# Eload_Power_Module_Support_-_Gen_2_Rev_4.net
KiCad netlist of a schematic drawn in Altium Designer
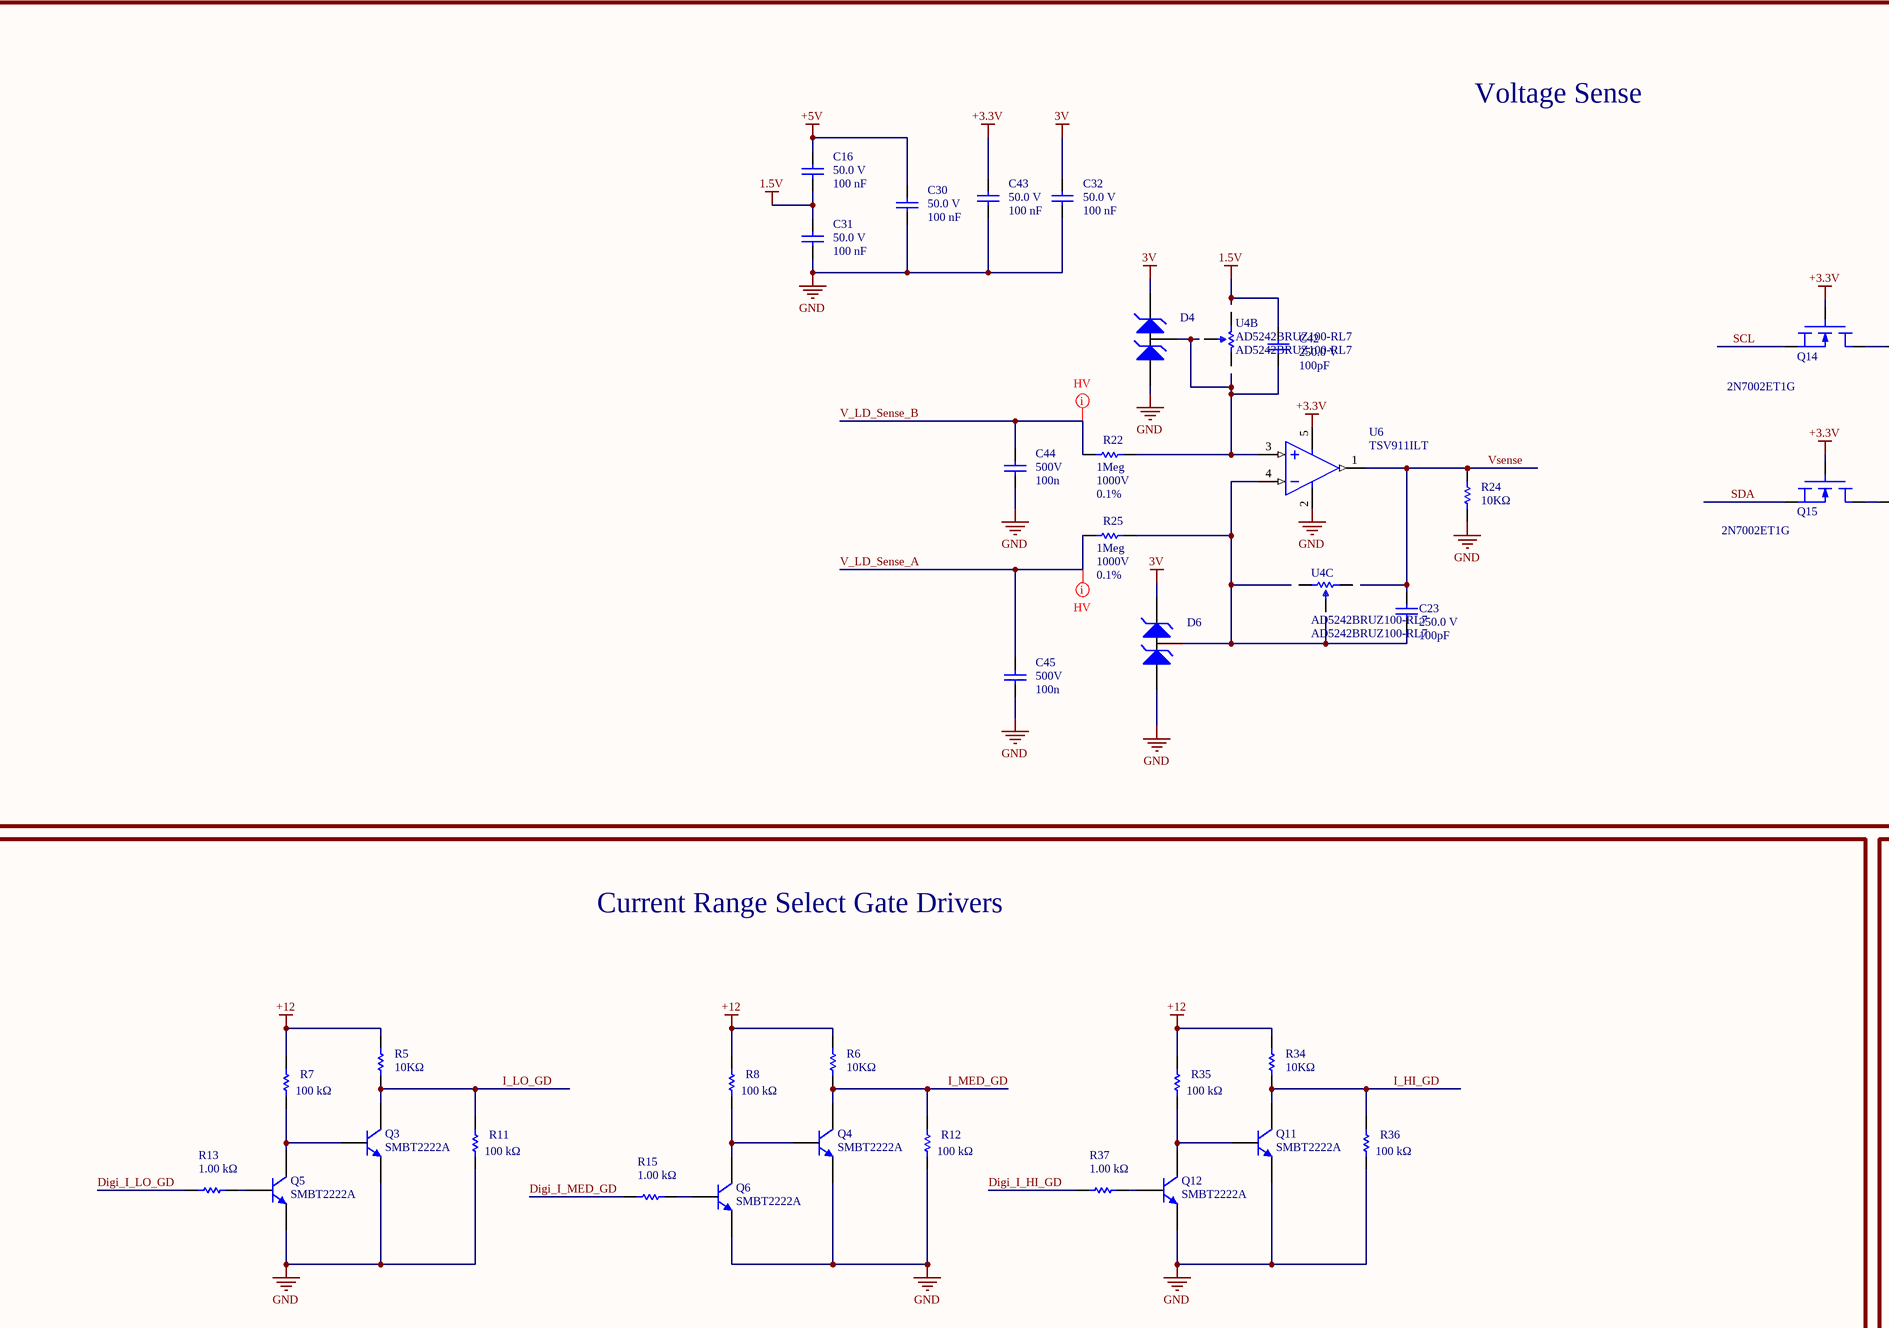
[diagram p0: Eload Power Module Support - Gen 2 Rev 4.SchDoc, top left]
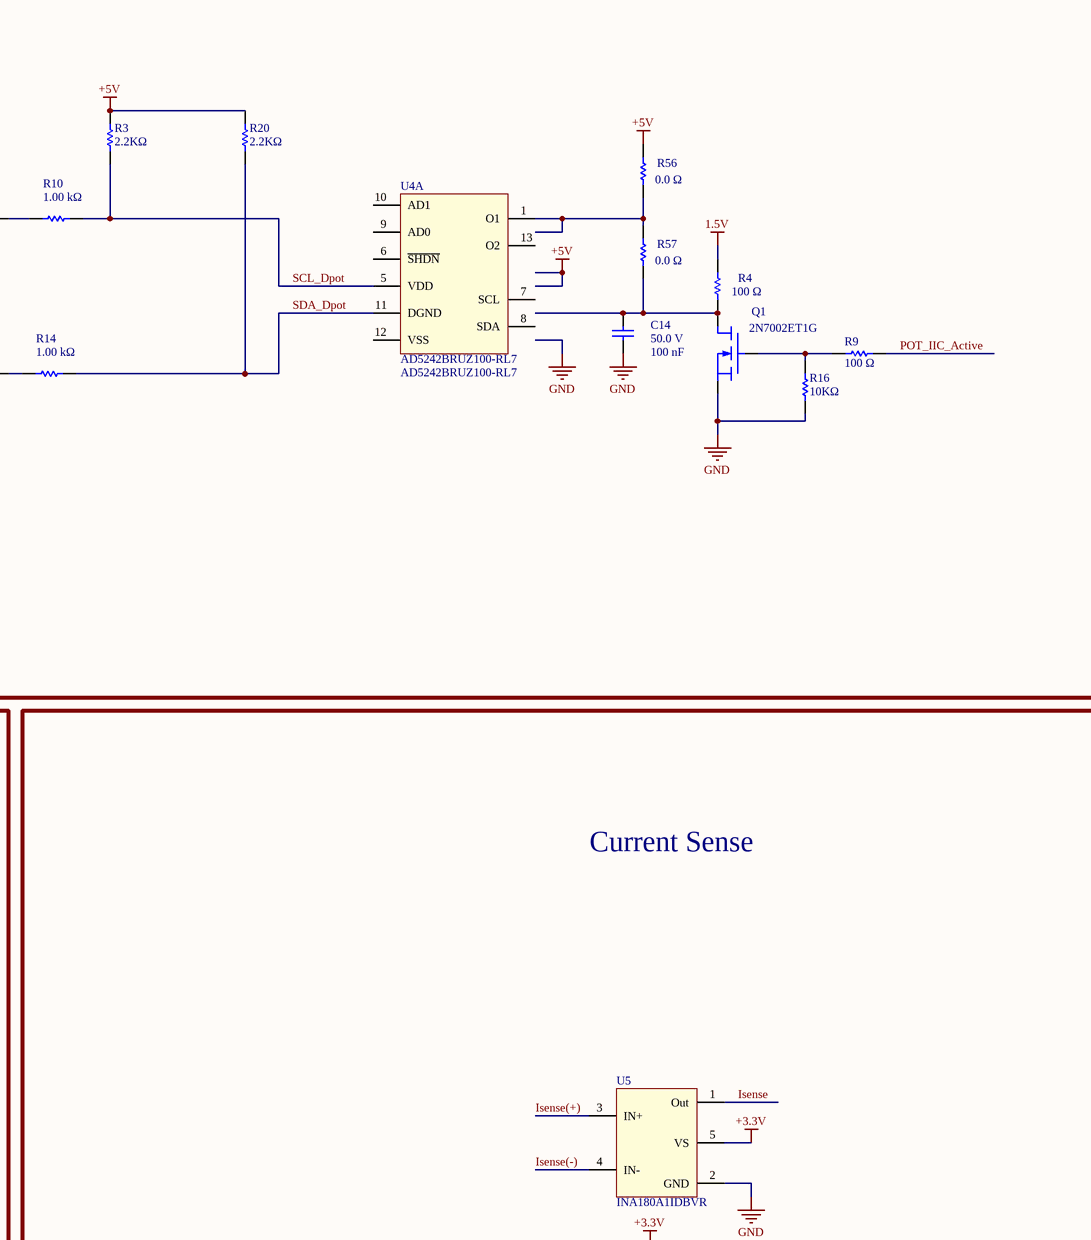
[diagram p1: Eload Power Module Support - Gen 2 Rev 4.SchDoc, top right]
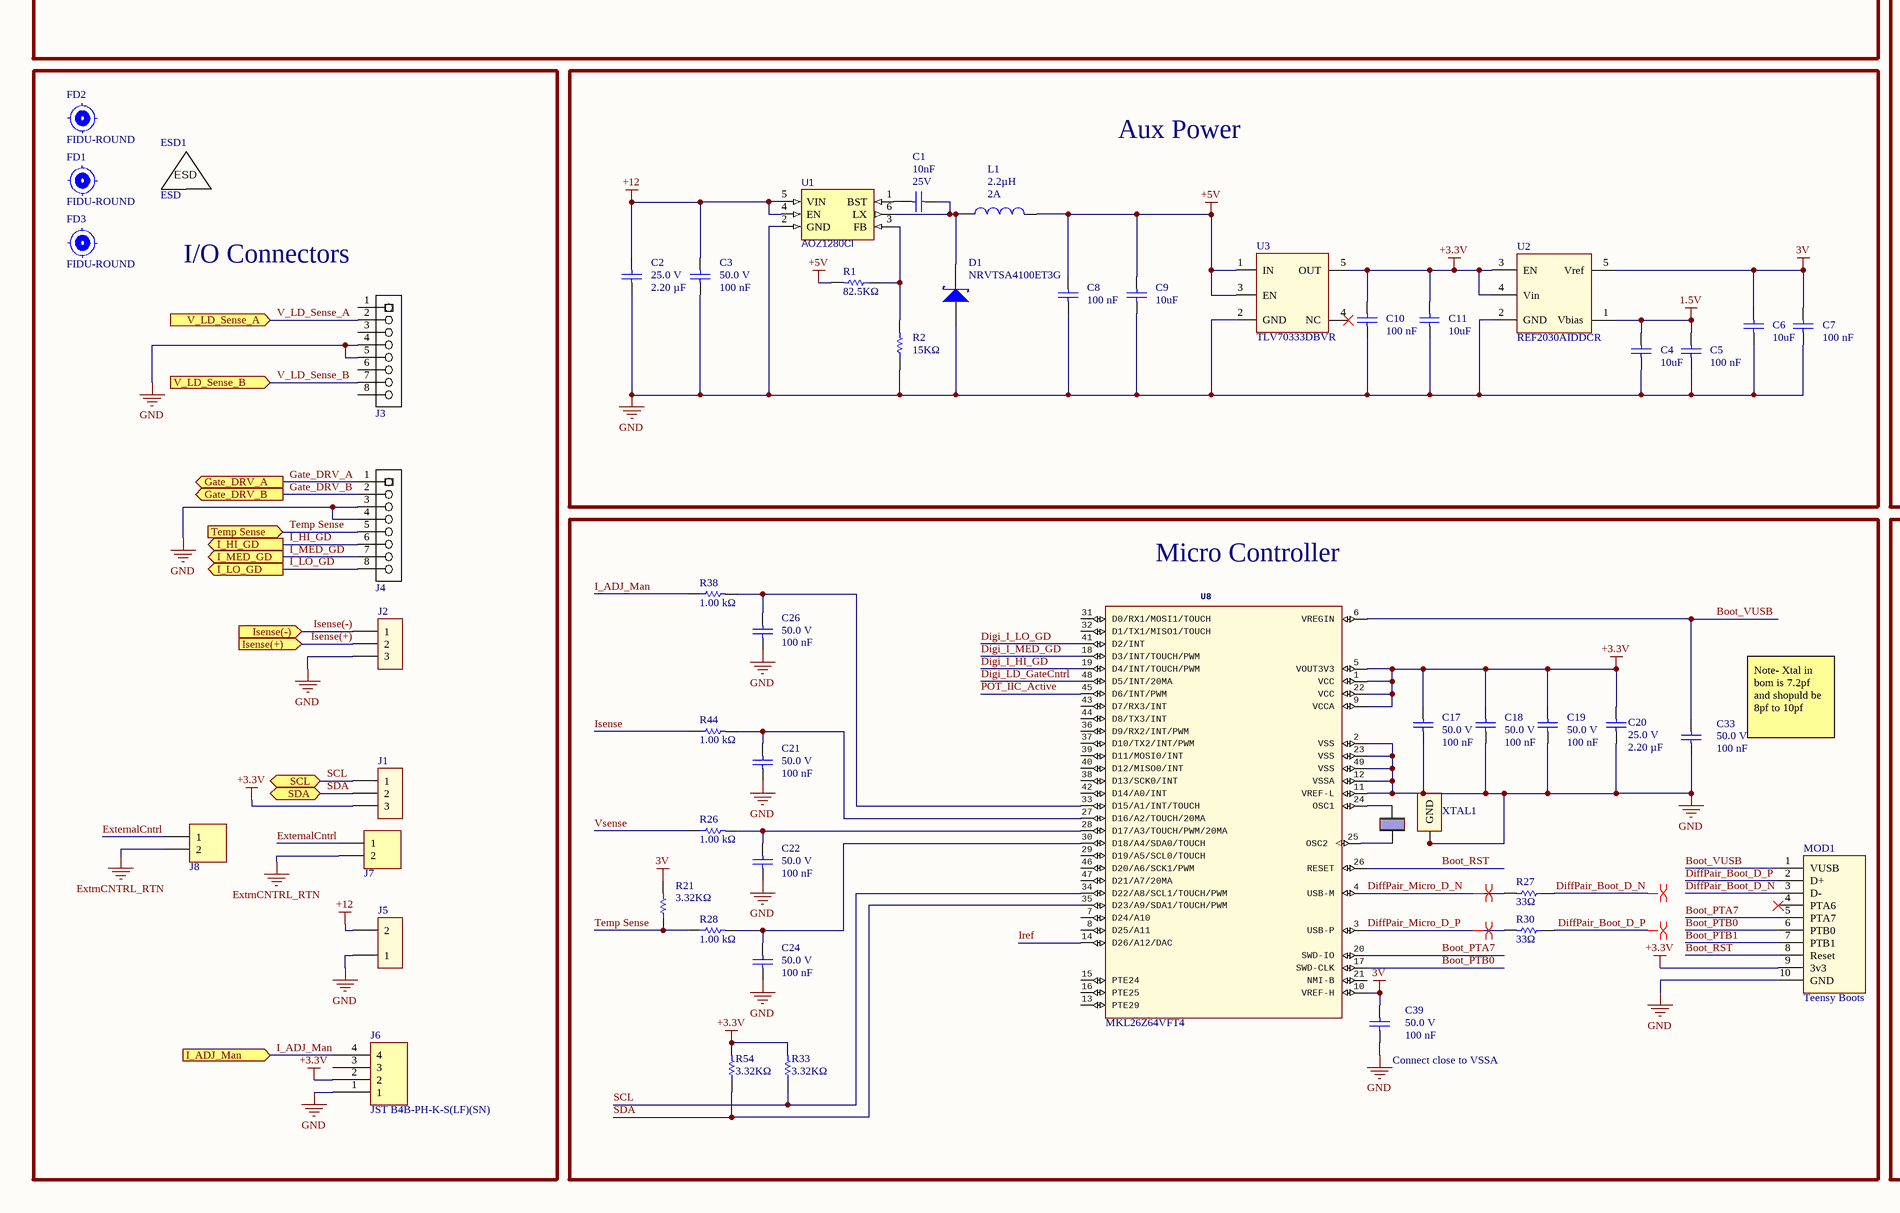
[diagram p2: Eload Power Module Support - Gen 2 Rev 4.SchDoc, bottom left]
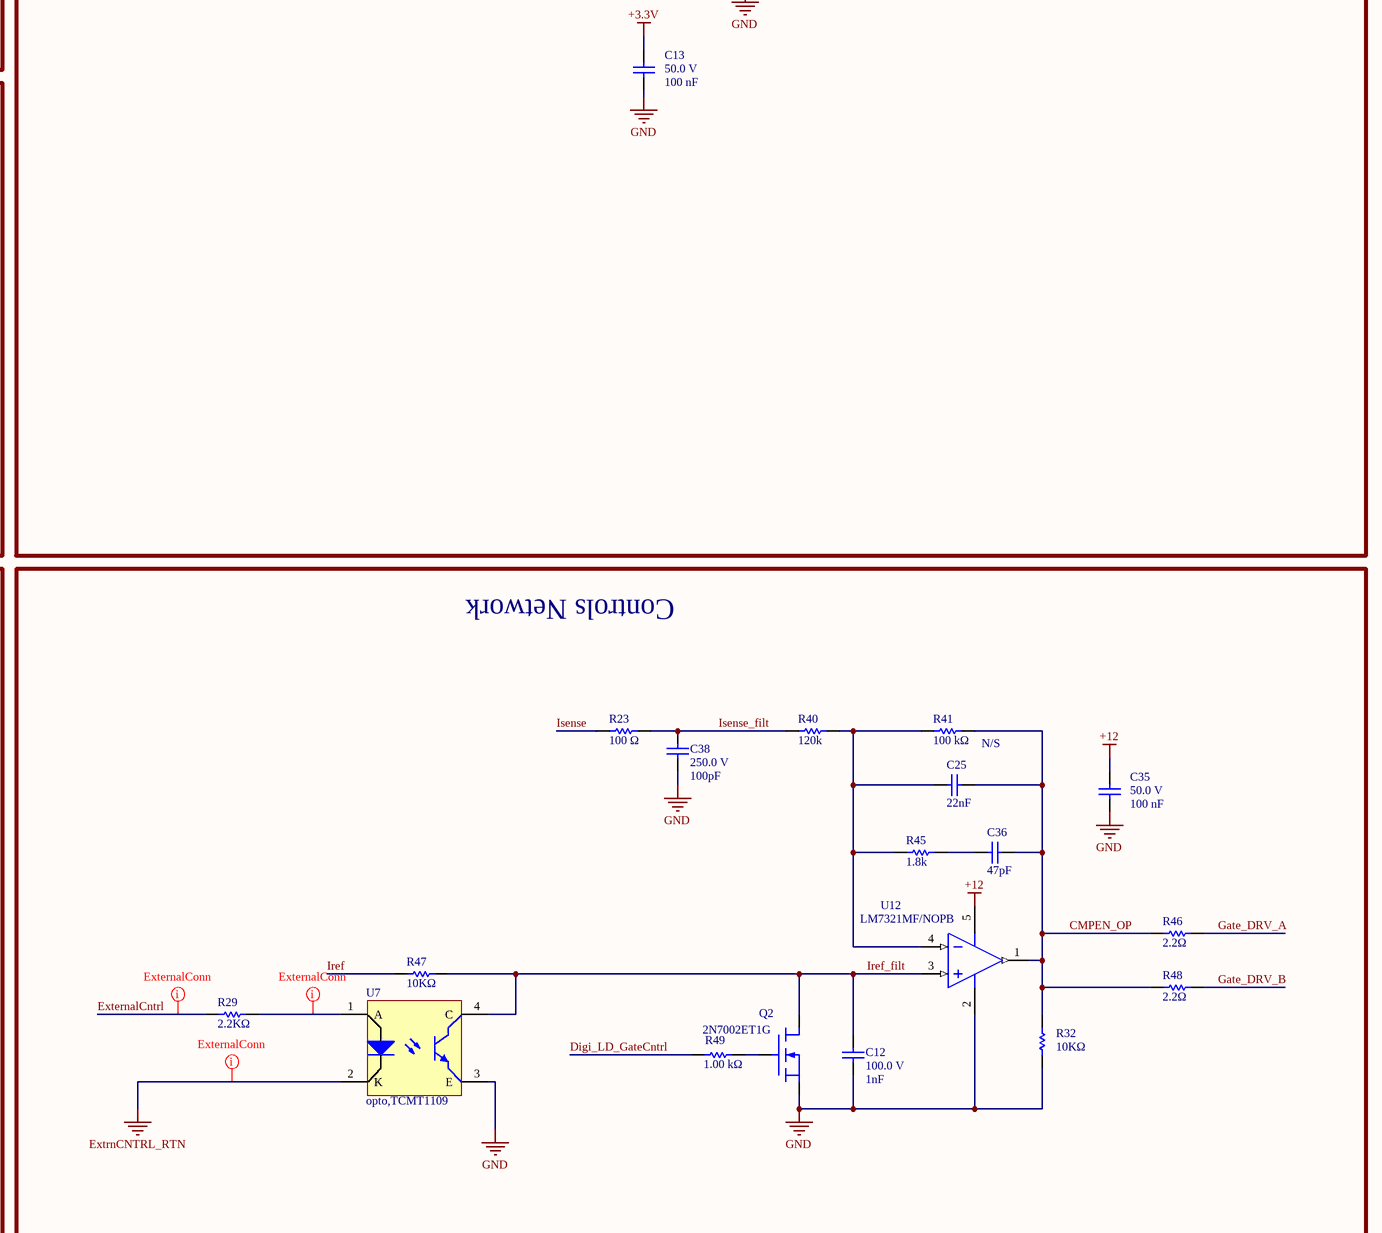
[diagram p3: Eload Power Module Support - Gen 2 Rev 4.SchDoc, bottom right]

(export (version "E")
  (design (tool "Eeschema 10.0.6"))
  (components
    (comp (ref "C1")
      (value "CL21B103KAANNNC")
      (footprint "Cap,0805")
      (description "CAP CER 10000PF 25V X7R 0805")
      (fields
        (field (name "MANUFACTURER") "Samsung Electro-Mechanics")
        (field (name "VOLTAGE RATING (DC)") "25V")
        (field (name "CAPACITANCE") "10nF")
      )
      (libsource (lib "Master Oct28_2018") (part "Cap,0805,10nF,±10%,25Vdc"))
    )
    (comp (ref "C2")
      (value "AVX 08053C225KAT2A")
      (footprint "CAP, 0805, HD")
      (description "0805 2.2 uF 25 V ±10 % Tolerance X7R SMT Multilayer Ceramic Capacitor")
      (fields
        (field (name "MANUFACTURER PART NUMBER") "08053C225KAT2A")
        (field (name "VOLTAGE RATING (DC)") "25.0 V")
        (field (name "CAPACITANCE") "2.20 µF")
      )
      (libsource (lib "Master Oct28_2018") (part "Cap,0805,2.2uF,25V,±10%"))
    )
    (comp (ref "C3")
      (value "08055C104JAT2A")
      (footprint "CAP, 0805, HD")
      (description "Capacitor; Ceramic; Cap 0.1 uF; Tol 5%; Vol-Rtg 50 VDC; SMT; 0805; X7R; Tape & Reel")
      (fields (field (name "VOLTAGE RATING (DC)") "50.0 V") (field (name "CAPACITANCE") "100 nF"))
      (libsource (lib "Master Oct28_2018") (part "Cap,0805,100nf,50V,5%,08055C104JAT2A"))
    )
    (comp (ref "C4")
      (value "Cap,0805,10uf,6.3V,10%,CL21A106KQFNNNG")
      (footprint "CAP, 0805, HD")
      (description "CL21 Series 10 uF 6.3V ±10 % Tolerance X5R SMT Multilayer Ceramic Capacitor")
      (fields (field (name "TOLERANCE") "±10%") (field (name "CAPACITANCE") "10uF"))
      (libsource (lib "Master Oct28_2018") (part "Cap,0805,10uf,6.3V,10%,CL21A106KQFNNNG"))
    )
    (comp (ref "C5")
      (value "08055C104JAT2A")
      (footprint "CAP, 0805, HD")
      (description "Capacitor; Ceramic; Cap 0.1 uF; Tol 5%; Vol-Rtg 50 VDC; SMT; 0805; X7R; Tape & Reel")
      (fields (field (name "CAPACITANCE") "100 nF"))
      (libsource (lib "Master Oct28_2018") (part "Cap,0805,100nf,50V,5%,08055C104JAT2A"))
    )
    (comp (ref "C6")
      (value "Cap,0805,10uf,6.3V,10%,CL21A106KQFNNNG")
      (footprint "CAP, 0805, HD")
      (description "CL21 Series 10 uF 6.3V ±10 % Tolerance X5R SMT Multilayer Ceramic Capacitor")
      (fields (field (name "TOLERANCE") "±10%") (field (name "CAPACITANCE") "10uF"))
      (libsource (lib "Master Oct28_2018") (part "Cap,0805,10uf,6.3V,10%,CL21A106KQFNNNG"))
    )
    (comp (ref "C7")
      (value "08055C104JAT2A")
      (footprint "CAP, 0805, HD")
      (description "Capacitor; Ceramic; Cap 0.1 uF; Tol 5%; Vol-Rtg 50 VDC; SMT; 0805; X7R; Tape & Reel")
      (fields (field (name "CAPACITANCE") "100 nF"))
      (libsource (lib "Master Oct28_2018") (part "Cap,0805,100nf,50V,5%,08055C104JAT2A"))
    )
    (comp (ref "C8")
      (value "08055C104JAT2A")
      (footprint "CAP, 0805, HD")
      (description "Capacitor; Ceramic; Cap 0.1 uF; Tol 5%; Vol-Rtg 50 VDC; SMT; 0805; X7R; Tape & Reel")
      (fields (field (name "CAPACITANCE") "100 nF"))
      (libsource (lib "Master Oct28_2018") (part "Cap,0805,100nf,50V,5%,08055C104JAT2A"))
    )
    (comp (ref "C9")
      (value "Cap,0805,10uf,6.3V,10%,CL21A106KQFNNNG")
      (footprint "CAP, 0805, HD")
      (description "CL21 Series 10 uF 6.3V ±10 % Tolerance X5R SMT Multilayer Ceramic Capacitor")
      (fields (field (name "TOLERANCE") "±10%") (field (name "CAPACITANCE") "10uF"))
      (libsource (lib "Master Oct28_2018") (part "Cap,0805,10uf,6.3V,10%,CL21A106KQFNNNG"))
    )
    (comp (ref "C10")
      (value "08055C104JAT2A")
      (footprint "CAP, 0805, HD")
      (description "Capacitor; Ceramic; Cap 0.1 uF; Tol 5%; Vol-Rtg 50 VDC; SMT; 0805; X7R; Tape & Reel")
      (fields (field (name "CAPACITANCE") "100 nF"))
      (libsource (lib "Master Oct28_2018") (part "Cap,0805,100nf,50V,5%,08055C104JAT2A"))
    )
    (comp (ref "C11")
      (value "Cap,0805,10uf,6.3V,10%,CL21A106KQFNNNG")
      (footprint "CAP, 0805, HD")
      (description "CL21 Series 10 uF 6.3V ±10 % Tolerance X5R SMT Multilayer Ceramic Capacitor")
      (fields (field (name "TOLERANCE") "±10%") (field (name "CAPACITANCE") "10uF"))
      (libsource (lib "Master Oct28_2018") (part "Cap,0805,10uf,6.3V,10%,CL21A106KQFNNNG"))
    )
    (comp (ref "C12")
      (value "Kemet C0805X102J1GACAUTO")
      (footprint "CAP, 0805, HD")
      (description "CAPACITOR, 1NF, 100V, NP0, 0805")
      (fields (field (name "VOLTAGE RATING (DC)") "100.0 V") (field (name "CAPACITANCE") "1nF"))
      (libsource (lib "Master SEPT2019") (part "Cap,0805,1nF,±5%,100Vdc"))
    )
    (comp (ref "C13")
      (value "08055C104JAT2A")
      (footprint "CAP, 0805, HD")
      (description "Capacitor; Ceramic; Cap 0.1 uF; Tol 5%; Vol-Rtg 50 VDC; SMT; 0805; X7R; Tape & Reel")
      (fields (field (name "VOLTAGE RATING (DC)") "50.0 V") (field (name "CAPACITANCE") "100 nF"))
      (libsource (lib "Master Oct28_2018") (part "Cap,0805,100nf,50V,5%,08055C104JAT2A"))
    )
    (comp (ref "C14")
      (value "08055C104JAT2A")
      (footprint "CAP, 0805, HD")
      (description "Capacitor; Ceramic; Cap 0.1 uF; Tol 5%; Vol-Rtg 50 VDC; SMT; 0805; X7R; Tape & Reel")
      (fields (field (name "VOLTAGE RATING (DC)") "50.0 V") (field (name "CAPACITANCE") "100 nF"))
      (libsource (lib "Master Oct28_2018") (part "Cap,0805,100nf,50V,5%,08055C104JAT2A"))
    )
    (comp (ref "C16")
      (value "08055C104JAT2A")
      (footprint "CAP, 0805, HD")
      (description "Capacitor; Ceramic; Cap 0.1 uF; Tol 5%; Vol-Rtg 50 VDC; SMT; 0805; X7R; Tape & Reel")
      (fields (field (name "VOLTAGE RATING (DC)") "50.0 V") (field (name "CAPACITANCE") "100 nF"))
      (libsource (lib "Master Oct28_2018") (part "Cap,0805,100nf,50V,5%,08055C104JAT2A"))
    )
    (comp (ref "C17")
      (value "Cap")
      (footprint "Cap,0805")
      (description "Capacitor; Ceramic; Cap 0.1 uF; Tol 5%; Vol-Rtg 50 VDC; SMT; 0805; X7R; Tape & Reel")
      (fields
        (field (name "MANUFACTURER PART NUMBER") "08055C104JAT2A")
        (field (name "VOLTAGE RATING (DC)") "50.0 V")
        (field (name "CAPACITANCE") "100 nF")
      )
      (libsource (lib "Master JULY2019") (part "Cap,0805,100nf,50V,5%,08055C104JAT2A"))
    )
    (comp (ref "C18")
      (value "Cap")
      (footprint "Cap,0805")
      (description "Capacitor; Ceramic; Cap 0.1 uF; Tol 5%; Vol-Rtg 50 VDC; SMT; 0805; X7R; Tape & Reel")
      (fields
        (field (name "MANUFACTURER PART NUMBER") "08055C104JAT2A")
        (field (name "VOLTAGE RATING (DC)") "50.0 V")
        (field (name "CAPACITANCE") "100 nF")
      )
      (libsource (lib "Master JULY2019") (part "Cap,0805,100nf,50V,5%,08055C104JAT2A"))
    )
    (comp (ref "C19")
      (value "Cap")
      (footprint "Cap,0805")
      (description "Capacitor; Ceramic; Cap 0.1 uF; Tol 5%; Vol-Rtg 50 VDC; SMT; 0805; X7R; Tape & Reel")
      (fields
        (field (name "MANUFACTURER PART NUMBER") "08055C104JAT2A")
        (field (name "VOLTAGE RATING (DC)") "50.0 V")
        (field (name "CAPACITANCE") "100 nF")
      )
      (libsource (lib "Master JULY2019") (part "Cap,0805,100nf,50V,5%,08055C104JAT2A"))
    )
    (comp (ref "C20")
      (value "AVX 08053C225KAT2A")
      (footprint "CAP, 0805, HD")
      (description "0805 2.2 uF 25 V ±10 % Tolerance X7R SMT Multilayer Ceramic Capacitor")
      (fields
        (field (name "MANUFACTURER PART NUMBER") "08053C225KAT2A")
        (field (name "VOLTAGE RATING (DC)") "25.0 V")
        (field (name "CAPACITANCE") "2.20 µF")
      )
      (libsource (lib "Master JULY2019") (part "Cap,0805,2.2uF,±10%,25V,08053C225KAT2A"))
    )
    (comp (ref "C21")
      (value "08055C104JAT2A")
      (footprint "CAP, 0805, HD")
      (description "Capacitor; Ceramic; Cap 0.1 uF; Tol 5%; Vol-Rtg 50 VDC; SMT; 0805; X7R; Tape & Reel")
      (fields (field (name "VOLTAGE RATING (DC)") "50.0 V") (field (name "CAPACITANCE") "100 nF"))
      (libsource (lib "Master Oct28_2018") (part "Cap,0805,100nf,50V,5%,08055C104JAT2A"))
    )
    (comp (ref "C22")
      (value "08055C104JAT2A")
      (footprint "CAP, 0805, HD")
      (description "Capacitor; Ceramic; Cap 0.1 uF; Tol 5%; Vol-Rtg 50 VDC; SMT; 0805; X7R; Tape & Reel")
      (fields (field (name "VOLTAGE RATING (DC)") "50.0 V") (field (name "CAPACITANCE") "100 nF"))
      (libsource (lib "Master Oct28_2018") (part "Cap,0805,100nf,50V,5%,08055C104JAT2A"))
    )
    (comp (ref "C23")
      (value "Cap")
      (footprint "Cap,0805")
      (description "CAP CER 100PF 250V 5% NP0 0805")
      (fields (field (name "VOLTAGE RATING (DC)") "250.0 V") (field (name "CAPACITANCE") "100pF"))
      (libsource (lib "Master JULY2019") (part "Cap,0805,100pf,250V,5%,GRM21A5C2E101JW01D"))
    )
    (comp (ref "C24")
      (value "08055C104JAT2A")
      (footprint "CAP, 0805, HD")
      (description "Capacitor; Ceramic; Cap 0.1 uF; Tol 5%; Vol-Rtg 50 VDC; SMT; 0805; X7R; Tape & Reel")
      (fields (field (name "VOLTAGE RATING (DC)") "50.0 V") (field (name "CAPACITANCE") "100 nF"))
      (libsource (lib "Master Oct28_2018") (part "Cap,0805,100nf,50V,5%,08055C104JAT2A"))
    )
    (comp (ref "C25")
      (value "Cap")
      (footprint "CAP, 0805, HD")
      (fields (field (name "CAP") "22nF"))
      (libsource (lib "Master SEPT2019") (part "CAP,0805,Generic"))
    )
    (comp (ref "C26")
      (value "08055C104JAT2A")
      (footprint "CAP, 0805, HD")
      (description "Capacitor; Ceramic; Cap 0.1 uF; Tol 5%; Vol-Rtg 50 VDC; SMT; 0805; X7R; Tape & Reel")
      (fields (field (name "VOLTAGE RATING (DC)") "50.0 V") (field (name "CAPACITANCE") "100 nF"))
      (libsource (lib "Master Oct28_2018") (part "Cap,0805,100nf,50V,5%,08055C104JAT2A"))
    )
    (comp (ref "C30")
      (value "08055C104JAT2A")
      (footprint "CAP, 0805, HD")
      (description "Capacitor; Ceramic; Cap 0.1 uF; Tol 5%; Vol-Rtg 50 VDC; SMT; 0805; X7R; Tape & Reel")
      (fields (field (name "VOLTAGE RATING (DC)") "50.0 V") (field (name "CAPACITANCE") "100 nF"))
      (libsource (lib "Master Oct28_2018") (part "Cap,0805,100nf,50V,5%,08055C104JAT2A"))
    )
    (comp (ref "C31")
      (value "08055C104JAT2A")
      (footprint "CAP, 0805, HD")
      (description "Capacitor; Ceramic; Cap 0.1 uF; Tol 5%; Vol-Rtg 50 VDC; SMT; 0805; X7R; Tape & Reel")
      (fields (field (name "VOLTAGE RATING (DC)") "50.0 V") (field (name "CAPACITANCE") "100 nF"))
      (libsource (lib "Master Oct28_2018") (part "Cap,0805,100nf,50V,5%,08055C104JAT2A"))
    )
    (comp (ref "C32")
      (value "08055C104JAT2A")
      (footprint "CAP, 0805, HD")
      (description "Capacitor; Ceramic; Cap 0.1 uF; Tol 5%; Vol-Rtg 50 VDC; SMT; 0805; X7R; Tape & Reel")
      (fields (field (name "VOLTAGE RATING (DC)") "50.0 V") (field (name "CAPACITANCE") "100 nF"))
      (libsource (lib "Master Oct28_2018") (part "Cap,0805,100nf,50V,5%,08055C104JAT2A"))
    )
    (comp (ref "C33")
      (value "Cap")
      (footprint "Cap,0805")
      (description "Capacitor; Ceramic; Cap 0.1 uF; Tol 5%; Vol-Rtg 50 VDC; SMT; 0805; X7R; Tape & Reel")
      (fields
        (field (name "MANUFACTURER PART NUMBER") "08055C104JAT2A")
        (field (name "VOLTAGE RATING (DC)") "50.0 V")
        (field (name "CAPACITANCE") "100 nF")
      )
      (libsource (lib "Master JULY2019") (part "Cap,0805,100nf,50V,5%,08055C104JAT2A"))
    )
    (comp (ref "C35")
      (value "08055C104JAT2A")
      (footprint "CAP, 0805, HD")
      (description "Capacitor; Ceramic; Cap 0.1 uF; Tol 5%; Vol-Rtg 50 VDC; SMT; 0805; X7R; Tape & Reel")
      (fields (field (name "VOLTAGE RATING (DC)") "50.0 V") (field (name "CAPACITANCE") "100 nF"))
      (libsource (lib "Master Oct28_2018") (part "Cap,0805,100nf,50V,5%,08055C104JAT2A"))
    )
    (comp (ref "C36")
      (value "Cap")
      (footprint "CAP, 0805, HD")
      (fields (field (name "CAP") "47pF"))
      (libsource (lib "Master SEPT2019") (part "CAP,0805,Generic"))
    )
    (comp (ref "C38")
      (value "Cap")
      (footprint "Cap,0805")
      (description "CAP CER 100PF 250V 5% NP0 0805")
      (fields (field (name "VOLTAGE RATING (DC)") "250.0 V") (field (name "CAPACITANCE") "100pF"))
      (libsource (lib "Master JULY2019") (part "Cap,0805,100pf,250V,5%,GRM21A5C2E101JW01D"))
    )
    (comp (ref "C39")
      (value "Cap")
      (footprint "Cap,0805")
      (description "Capacitor; Ceramic; Cap 0.1 uF; Tol 5%; Vol-Rtg 50 VDC; SMT; 0805; X7R; Tape & Reel")
      (fields
        (field (name "MANUFACTURER PART NUMBER") "08055C104JAT2A")
        (field (name "VOLTAGE RATING (DC)") "50.0 V")
        (field (name "CAPACITANCE") "100 nF")
      )
      (libsource (lib "Master JULY2019") (part "Cap,0805,100nf,50V,5%,08055C104JAT2A"))
    )
    (comp (ref "C42")
      (value "Cap")
      (footprint "Cap,0805")
      (description "CAP CER 100PF 250V 5% NP0 0805")
      (fields (field (name "VOLTAGE RATING (DC)") "250.0 V") (field (name "CAPACITANCE") "100pF"))
      (libsource (lib "Master JULY2019") (part "Cap,0805,100pf,250V,5%,GRM21A5C2E101JW01D"))
    )
    (comp (ref "C43")
      (value "08055C104JAT2A")
      (footprint "CAP, 0805, HD")
      (description "Capacitor; Ceramic; Cap 0.1 uF; Tol 5%; Vol-Rtg 50 VDC; SMT; 0805; X7R; Tape & Reel")
      (fields (field (name "VOLTAGE RATING (DC)") "50.0 V") (field (name "CAPACITANCE") "100 nF"))
      (libsource (lib "Master Oct28_2018") (part "Cap,0805,100nf,50V,5%,08055C104JAT2A"))
    )
    (comp (ref "C44")
      (value "Cap")
      (footprint "Cap,1210")
      (fields (field (name "CAP") "100n") (field (name "VOLT") "500V"))
      (libsource (lib "Master SEPT2019") (part "CAP,1210,Generic"))
    )
    (comp (ref "C45")
      (value "Cap")
      (footprint "Cap,1210")
      (fields (field (name "CAP") "100n") (field (name "VOLT") "500V"))
      (libsource (lib "Master SEPT2019") (part "CAP,1210,Generic"))
    )
    (comp (ref "D1")
      (value "NRVTSA4100ET3G")
      (footprint "DO-214AC, SMA")
      (description "Trench Schottky Rectifier, Very Low Leakage, 100V, 4A")
      (fields (field (name "MFG ~{P}N") "NRVTSA4100ET3G") (field (name "MANUFACTURER") "ON Semiconductor"))
      (libsource (lib "Master Oct28_2018") (part "Dio,Schottky,4A,400V,NRVTSA4100ET3G"))
    )
    (comp (ref "D4")
      (value "Diode")
      (footprint "SOT23-3")
      (fields (field (name "BASE PART NUMBER") "BAT54SL") (field (name "MANUFACTURER") "ON Semiconductor"))
      (libsource (lib "Master JULY2019") (part "Diode,Shottky,Array,Series,30V,200mA,BAT54SLT1G"))
    )
    (comp (ref "D6")
      (value "Diode")
      (footprint "SOT23-3")
      (fields (field (name "BASE PART NUMBER") "BAT54SL") (field (name "MANUFACTURER") "ON Semiconductor"))
      (libsource (lib "Master JULY2019") (part "Diode,Shottky,Array,Series,30V,200mA,BAT54SLT1G"))
    )
    (comp (ref "ESD1")
      (value "ESD")
      (footprint "ESDSILK")
      (description "ESD LOGO")
      (libsource (lib "TH Mechanical") (part "ESD"))
    )
    (comp (ref "FD1")
      (value "FIDU-ROUND")
      (footprint "FIDU-ROUND")
      (description "ROUND FIDUCIAL")
      (libsource (lib "TH Mechanical") (part "FIDU-ROUND"))
    )
    (comp (ref "FD2")
      (value "FIDU-ROUND")
      (footprint "FIDU-ROUND")
      (description "ROUND FIDUCIAL")
      (libsource (lib "TH Mechanical") (part "FIDU-ROUND"))
    )
    (comp (ref "FD3")
      (value "FIDU-ROUND")
      (footprint "FIDU-ROUND")
      (description "ROUND FIDUCIAL")
      (libsource (lib "TH Mechanical") (part "FIDU-ROUND"))
    )
    (comp (ref "J1")
      (value "Generic Header")
      (footprint "Header,3POS,0.1\",RA")
      (description "Generic Header 3 pos header 0.1\"")
      (libsource (lib "Master JULY2019") (part "Header 1x3,0.1{dblquote},TH,Generic"))
    )
    (comp (ref "J2")
      (value "Generic Header")
      (footprint "Header,3POS,0.1\",RA")
      (description "Generic Header 3 pos header 0.1\"")
      (libsource (lib "Master JULY2019") (part "Header 1x3,0.1{dblquote},TH,Generic"))
    )
    (comp (ref "J3")
      (value "HEADER,0.1\",8Pin,SinlgeRow")
      (footprint "Header,8Pin,SingleRow, RA,0.1\"")
      (libsource (lib "Master JULY2019") (part "HEADER,0.1{dblquote},8Pin,SinlgeRow"))
    )
    (comp (ref "J4")
      (value "HEADER,0.1\",8Pin,SinlgeRow")
      (footprint "Header,8Pin,SingleRow, RA,0.1\"")
      (libsource (lib "Master JULY2019") (part "HEADER,0.1{dblquote},8Pin,SinlgeRow"))
    )
    (comp (ref "J5")
      (value "Generic Header")
      (footprint "HEADER-1X2,0.1\",RA1")
      (libsource (lib "Master JULY2019") (part "Header 1x2,0.1{dblquote}Spacing"))
    )
    (comp (ref "J6")
      (value "JST B4B-PH-K-S(LF)(SN)")
      (footprint "Conn, JST, 4 pin, 2mm spacing")
      (description "PH Series 4 Position 2 mm Pitch Through Hole Crimp Top Entry Shrouded Header")
      (fields (field (name "MANUFACTURER PART NUMBER") "B4B-PH-K-S(LF)(SN)"))
      (libsource (lib "Master JULY2019") (part "Conntector, though hole, JST, 4pin, 2mm,B4B-PH-K-S(LF)(SN)"))
    )
    (comp (ref "J7")
      (value "conn, through hole, molex, 2 pin, 0.1\",640456-2")
      (footprint "Conn, Molex, 2pin,0.1\" spacing")
      (description "Header, Friction Lock; MTA-100; 2; 250 VAC; Polyester; Tin; Copper Alloy; Tin")
      (libsource (lib "Master JULY2019") (part "conn, through hole, molex, 2 pin, 0.1{dblquote},640456-2"))
    )
    (comp (ref "J8")
      (value "conn, through hole, molex, 2 pin, 0.1\",640456-2")
      (footprint "Conn, Molex, 2pin,0.1\" spacing")
      (description "Header, Friction Lock; MTA-100; 2; 250 VAC; Polyester; Tin; Copper Alloy; Tin")
      (libsource (lib "Master JULY2019") (part "conn, through hole, molex, 2 pin, 0.1{dblquote},640456-2"))
    )
    (comp (ref "L1")
      (value "CIGT252008LM2R2MNE")
      (footprint "IND,2520")
      (description "FIXED IND 2.2UH 2A 97MOHM SMD")
      (fields
        (field (name "MANUFACTURER") "Samsung Electro-Mechanics")
        (field (name "INDUCTANCE") "2.2µH")
        (field (name "TOLERANCE") "±20%")
        (field (name "CURRENT RATING (AMPS)") "2A")
      )
      (libsource (lib "Master Oct28_2018") (part "IND,2025,2.2u,2A,97mOhm,CIGT252008LM2R2MNE"))
    )
    (comp (ref "MOD1")
      (value "Teensy Boots")
      (footprint "Mod,Teensy Boots")
      (libsource (lib "Master SEPT2019") (part "Module,Teensy Boots,Programming"))
    )
    (comp (ref "Q1")
      (value "2N7002ET1G")
      (footprint "SOT23-3")
      (description "Small Signal MOSFET, 60 V, 310 mA, Single, N-Channel, 3-Pin SOT-23, Pb-Free, Tape and Reel")
      (fields
        (field (name "MANUFACTURER") "ON Semiconductor")
        (field (name "MANUFACTURER PART NUMBER") "2N7002ET1G")
      )
      (libsource (lib "Master JULY2019") (part "MOSFET,N-Channel,SOT23,0.25A,60V,2N7002ET1G"))
    )
    (comp (ref "Q2")
      (value "2N7002ET1G")
      (footprint "SOT23-3")
      (description "Small Signal MOSFET, 60 V, 310 mA, Single, N-Channel, 3-Pin SOT-23, Pb-Free, Tape and Reel")
      (fields
        (field (name "MANUFACTURER") "ON Semiconductor")
        (field (name "MANUFACTURER PART NUMBER") "2N7002ET1G")
      )
      (libsource (lib "Master JULY2019") (part "MOSFET,N-Channel,SOT23,0.25A,60V,2N7002ET1G"))
    )
    (comp (ref "Q3")
      (value "SMBT2222A")
      (footprint "SOT23-3")
      (description "NPN Silicon Switching Transistor, 40 V VCEO, 600 mA IC, SOT23, Reel, Green")
      (fields (field (name "MFG P/N") "SMBT2222A"))
      (libsource (lib "Master JULY2019") (part "Trans,40V,600mA,0.33W, SMBT2222A"))
    )
    (comp (ref "Q4")
      (value "SMBT2222A")
      (footprint "SOT23-3")
      (description "NPN Silicon Switching Transistor, 40 V VCEO, 600 mA IC, SOT23, Reel, Green")
      (fields (field (name "MFG P/N") "SMBT2222A"))
      (libsource (lib "Master JULY2019") (part "Trans,40V,600mA,0.33W, SMBT2222A"))
    )
    (comp (ref "Q5")
      (value "SMBT2222A")
      (footprint "SOT23-3")
      (description "NPN Silicon Switching Transistor, 40 V VCEO, 600 mA IC, SOT23, Reel, Green")
      (fields (field (name "MFG P/N") "SMBT2222A"))
      (libsource (lib "Master JULY2019") (part "Trans,40V,600mA,0.33W, SMBT2222A"))
    )
    (comp (ref "Q6")
      (value "SMBT2222A")
      (footprint "SOT23-3")
      (description "NPN Silicon Switching Transistor, 40 V VCEO, 600 mA IC, SOT23, Reel, Green")
      (fields (field (name "MFG P/N") "SMBT2222A"))
      (libsource (lib "Master JULY2019") (part "Trans,40V,600mA,0.33W, SMBT2222A"))
    )
    (comp (ref "Q11")
      (value "SMBT2222A")
      (footprint "SOT23-3")
      (description "NPN Silicon Switching Transistor, 40 V VCEO, 600 mA IC, SOT23, Reel, Green")
      (fields (field (name "MFG P/N") "SMBT2222A"))
      (libsource (lib "Master JULY2019") (part "Trans,40V,600mA,0.33W, SMBT2222A"))
    )
    (comp (ref "Q12")
      (value "SMBT2222A")
      (footprint "SOT23-3")
      (description "NPN Silicon Switching Transistor, 40 V VCEO, 600 mA IC, SOT23, Reel, Green")
      (fields (field (name "MFG P/N") "SMBT2222A"))
      (libsource (lib "Master JULY2019") (part "Trans,40V,600mA,0.33W, SMBT2222A"))
    )
    (comp (ref "Q14")
      (value "2N7002ET1G")
      (footprint "SOT23-3")
      (description "Small Signal MOSFET, 60 V, 310 mA, Single, N-Channel, 3-Pin SOT-23, Pb-Free, Tape and Reel")
      (fields
        (field (name "MANUFACTURER") "ON Semiconductor")
        (field (name "MANUFACTURER PART NUMBER") "2N7002ET1G")
      )
      (libsource (lib "Master JULY2019") (part "MOSFET,N-Channel,SOT23,0.25A,60V,2N7002ET1G"))
    )
    (comp (ref "Q15")
      (value "2N7002ET1G")
      (footprint "SOT23-3")
      (description "Small Signal MOSFET, 60 V, 310 mA, Single, N-Channel, 3-Pin SOT-23, Pb-Free, Tape and Reel")
      (fields
        (field (name "MANUFACTURER") "ON Semiconductor")
        (field (name "MANUFACTURER PART NUMBER") "2N7002ET1G")
      )
      (libsource (lib "Master JULY2019") (part "MOSFET,N-Channel,SOT23,0.25A,60V,2N7002ET1G"))
    )
    (comp (ref "R1")
      (value "TNPW080582K5BEEA")
      (footprint "res, 0805, HD")
      (fields
        (field (name "MANUFACTURER") "Vishay Dale")
        (field (name "TOLERANCE") "±0.1%")
        (field (name "RESISTANCE") "82.5KΩ")
      )
      (libsource (lib "Master JULY2019") (part "Res,0805,82.5KΩ,0.1%,25ppm, TNPW080582K5BEEA"))
    )
    (comp (ref "R2")
      (value "CRGCQ0805F15K")
      (footprint "res, 0805, HD")
      (fields (field (name "TOLERANCE") "±1%") (field (name "RESISTANCE") "15KΩ"))
      (libsource (lib "Master Oct28_2018") (part "Res,0805,15KΩ,1%,±100ppm/°C,CRGCQ0805F15K"))
    )
    (comp (ref "R3")
      (value "Res1")
      (footprint "res, 0805, HD")
      (description "RES SMD 2.2K OHM 1% 1/8W 0805")
      (fields (field (name "RESISTANCE") "2.2KΩ"))
      (libsource (lib "Master SEPT2019") (part "Res,0805,2.2KΩ,±1%,100.0 ppm/°C,150.0 V,CRCW08052K20FKEA"))
    )
    (comp (ref "R4")
      (value "CRCW0805100RJNEAC")
      (footprint "res, 0805, HD")
      (description "RES 100 OHM 5% 1/8W 0805")
      (fields (field (name "TOLERANCE") "±5%") (field (name "RESISTANCE") "100 Ω"))
      (libsource (lib "Master SEPT2019") (part "Res,0805,100Ω,5%,±200ppm/°C"))
    )
    (comp (ref "R5")
      (value "Vishay / Dale CRCW080510K0FKTA")
      (footprint "res, 0805, HD")
      (description "RES SMD 10K OHM 1% 1/8W 0805")
      (fields (field (name "RESISTANCE") "10KΩ"))
      (libsource (lib "Master Oct28_2018") (part "Res,0805,10.0kΩ,1%,100 ppm,CRCW080510K0FKTA"))
    )
    (comp (ref "R6")
      (value "Vishay / Dale CRCW080510K0FKTA")
      (footprint "res, 0805, HD")
      (description "RES SMD 10K OHM 1% 1/8W 0805")
      (fields (field (name "RESISTANCE") "10KΩ"))
      (libsource (lib "Master Oct28_2018") (part "Res,0805,10.0kΩ,1%,100 ppm,CRCW080510K0FKTA"))
    )
    (comp (ref "R7")
      (value "Res,0805,100kΩ,1%,100ppm,CRCW0805100KFKEA")
      (footprint "res, 0805, HD")
      (description "100 kOhms ±1% 0.125W, 1/8W Chip Resistor 0805 (2012 Metric) Thick Film")
      (fields
        (field (name "MANUFACTURER PART NUMBER") "CRCW0805100KFKEA")
        (field (name "MANUFACTURER") "Vishay")
        (field (name "RESISTANCE") "100 kΩ")
      )
      (libsource (lib "Master Oct28_2018") (part "Res,0805,100kΩ,1%,100ppm,CRCW0805100KFKEA"))
    )
    (comp (ref "R8")
      (value "Res,0805,100kΩ,1%,100ppm,CRCW0805100KFKEA")
      (footprint "res, 0805, HD")
      (description "100 kOhms ±1% 0.125W, 1/8W Chip Resistor 0805 (2012 Metric) Thick Film")
      (fields
        (field (name "MANUFACTURER PART NUMBER") "CRCW0805100KFKEA")
        (field (name "MANUFACTURER") "Vishay")
        (field (name "RESISTANCE") "100 kΩ")
      )
      (libsource (lib "Master Oct28_2018") (part "Res,0805,100kΩ,1%,100ppm,CRCW0805100KFKEA"))
    )
    (comp (ref "R9")
      (value "CRCW0805100RJNEAC")
      (footprint "res, 0805, HD")
      (description "RES 100 OHM 5% 1/8W 0805")
      (fields (field (name "TOLERANCE") "±5%") (field (name "RESISTANCE") "100 Ω"))
      (libsource (lib "Master SEPT2019") (part "Res,0805,100Ω,5%,±200ppm/°C"))
    )
    (comp (ref "R10")
      (value "Vishay CRCW08051K00JNEA")
      (footprint "res, 0805, HD")
      (description "Res Thick Film 0805 1K Ohm 5% 0.125W(1/8W) ±200ppm/C Molded SMD Automotive Paper T/R")
      (fields
        (field (name "MANUFACTURER PART NUMBER") "CRCW08051K00JNEA")
        (field (name "RESISTANCE") "1.00 kΩ")
      )
      (libsource (lib "Master Oct28_2018") (part "Res,0805,1.00 kΩ,5%,200ppm,CRCW08051K00JNEA"))
    )
    (comp (ref "R11")
      (value "Res,0805,100kΩ,1%,100ppm,CRCW0805100KFKEA")
      (footprint "res, 0805, HD")
      (description "100 kOhms ±1% 0.125W, 1/8W Chip Resistor 0805 (2012 Metric) Thick Film")
      (fields
        (field (name "MANUFACTURER PART NUMBER") "CRCW0805100KFKEA")
        (field (name "MANUFACTURER") "Vishay")
        (field (name "RESISTANCE") "100 kΩ")
      )
      (libsource (lib "Master Oct28_2018") (part "Res,0805,100kΩ,1%,100ppm,CRCW0805100KFKEA"))
    )
    (comp (ref "R12")
      (value "Res,0805,100kΩ,1%,100ppm,CRCW0805100KFKEA")
      (footprint "res, 0805, HD")
      (description "100 kOhms ±1% 0.125W, 1/8W Chip Resistor 0805 (2012 Metric) Thick Film")
      (fields
        (field (name "MANUFACTURER PART NUMBER") "CRCW0805100KFKEA")
        (field (name "MANUFACTURER") "Vishay")
        (field (name "RESISTANCE") "100 kΩ")
      )
      (libsource (lib "Master Oct28_2018") (part "Res,0805,100kΩ,1%,100ppm,CRCW0805100KFKEA"))
    )
    (comp (ref "R13")
      (value "Vishay CRCW08051K00JNEA")
      (footprint "res, 0805, HD")
      (description "Res Thick Film 0805 1K Ohm 5% 0.125W(1/8W) ±200ppm/C Molded SMD Automotive Paper T/R")
      (fields
        (field (name "MANUFACTURER PART NUMBER") "CRCW08051K00JNEA")
        (field (name "RESISTANCE") "1.00 kΩ")
      )
      (libsource (lib "Master Oct28_2018") (part "Res,0805,1.00 kΩ,5%,200ppm,CRCW08051K00JNEA"))
    )
    (comp (ref "R14")
      (value "Vishay CRCW08051K00JNEA")
      (footprint "res, 0805, HD")
      (description "Res Thick Film 0805 1K Ohm 5% 0.125W(1/8W) ±200ppm/C Molded SMD Automotive Paper T/R")
      (fields
        (field (name "MANUFACTURER PART NUMBER") "CRCW08051K00JNEA")
        (field (name "RESISTANCE") "1.00 kΩ")
      )
      (libsource (lib "Master Oct28_2018") (part "Res,0805,1.00 kΩ,5%,200ppm,CRCW08051K00JNEA"))
    )
    (comp (ref "R15")
      (value "Vishay CRCW08051K00JNEA")
      (footprint "res, 0805, HD")
      (description "Res Thick Film 0805 1K Ohm 5% 0.125W(1/8W) ±200ppm/C Molded SMD Automotive Paper T/R")
      (fields
        (field (name "MANUFACTURER PART NUMBER") "CRCW08051K00JNEA")
        (field (name "RESISTANCE") "1.00 kΩ")
      )
      (libsource (lib "Master Oct28_2018") (part "Res,0805,1.00 kΩ,5%,200ppm,CRCW08051K00JNEA"))
    )
    (comp (ref "R16")
      (value "Vishay / Dale CRCW080510K0FKTA")
      (footprint "res, 0805, HD")
      (description "RES SMD 10K OHM 1% 1/8W 0805")
      (fields (field (name "RESISTANCE") "10KΩ"))
      (libsource (lib "Master SEPT2019") (part "Res,0805,10.0kΩ,1%,100 ppm,CRCW080510K0FKTA"))
    )
    (comp (ref "R20")
      (value "Res1")
      (footprint "res, 0805, HD")
      (description "RES SMD 2.2K OHM 1% 1/8W 0805")
      (fields (field (name "RESISTANCE") "2.2KΩ"))
      (libsource (lib "Master SEPT2019") (part "Res,0805,2.2KΩ,±1%,100.0 ppm/°C,150.0 V,CRCW08052K20FKEA"))
    )
    (comp (ref "R21")
      (value "Res1")
      (footprint "res, 0805, HD")
      (description "RES SMD 3.32K OHM 1% 1/8W 0805")
      (fields (field (name "RESISTANCE") "3.32KΩ"))
      (libsource (lib "Master JULY2019") (part "Res,0805,3.32K,±1%,100.0 ppm/°C,150.0 V,CRCW08053K32FKEA"))
    )
    (comp (ref "R22")
      (value "TNPV12061M00BXEN")
      (footprint "Res,1206")
      (description "RES SMD 1M OHM 0.1% 1/4W 1206")
      (fields
        (field (name "RESISTANCE") "1Meg")
        (field (name "MAX VOLTAGE RATING") "1000V")
        (field (name "TOLERANCE") "0.1%")
      )
      (libsource (lib "Master Oct28_2018") (part "Res,1206,1Meg Ω,0.1%,±15ppm/°C,0.25W,TNPV12061M00BXEN"))
    )
    (comp (ref "R23")
      (value "CRCW0805100RJNEAC")
      (footprint "res, 0805, HD")
      (description "RES 100 OHM 5% 1/8W 0805")
      (fields (field (name "TOLERANCE") "±5%") (field (name "RESISTANCE") "100 Ω"))
      (libsource (lib "Master Mar2021") (part "Res,0805,100Ω,5%,±200ppm/°C"))
    )
    (comp (ref "R24")
      (value "Vishay / Dale CRCW080510K0FKTA")
      (footprint "res, 0805, HD")
      (description "RES SMD 10K OHM 1% 1/8W 0805")
      (fields (field (name "RESISTANCE") "10KΩ"))
      (libsource (lib "Master Oct28_2018") (part "Res,0805,10.0kΩ,1%,100 ppm,CRCW080510K0FKTA"))
    )
    (comp (ref "R25")
      (value "TNPV12061M00BXEN")
      (footprint "Res,1206")
      (description "RES SMD 1M OHM 0.1% 1/4W 1206")
      (fields
        (field (name "RESISTANCE") "1Meg")
        (field (name "MAX VOLTAGE RATING") "1000V")
        (field (name "TOLERANCE") "0.1%")
      )
      (libsource (lib "Master Oct28_2018") (part "Res,1206,1Meg Ω,0.1%,±15ppm/°C,0.25W,TNPV12061M00BXEN"))
    )
    (comp (ref "R26")
      (value "Vishay CRCW08051K00JNEA")
      (footprint "res, 0805, HD")
      (description "Res Thick Film 0805 1K Ohm 5% 0.125W(1/8W) ±200ppm/C Molded SMD Automotive Paper T/R")
      (fields
        (field (name "MANUFACTURER PART NUMBER") "CRCW08051K00JNEA")
        (field (name "RESISTANCE") "1.00 kΩ")
      )
      (libsource (lib "Master Oct28_2018") (part "Res,0805,1.00 kΩ,5%,200ppm,CRCW08051K00JNEA"))
    )
    (comp (ref "R27")
      (value "CR0805-JW-330ELF")
      (footprint "res, 0805, HD")
      (description "RES SMD 33 OHM 5% 1/8W 0805")
      (fields
        (field (name "MANUFACTURER") "Bourns Inc.")
        (field (name "TOLERANCE") "±5%")
        (field (name "RESISTANCE") "33Ω")
      )
      (libsource (lib "Master JULY2019") (part "Res,0805,33Ω,±5%,200ppm,CR0805-JW-330ELF"))
    )
    (comp (ref "R28")
      (value "Vishay CRCW08051K00JNEA")
      (footprint "res, 0805, HD")
      (description "Res Thick Film 0805 1K Ohm 5% 0.125W(1/8W) ±200ppm/C Molded SMD Automotive Paper T/R")
      (fields
        (field (name "MANUFACTURER PART NUMBER") "CRCW08051K00JNEA")
        (field (name "RESISTANCE") "1.00 kΩ")
      )
      (libsource (lib "Master Oct28_2018") (part "Res,0805,1.00 kΩ,5%,200ppm,CRCW08051K00JNEA"))
    )
    (comp (ref "R29")
      (value "CRCW08052K20FKEA")
      (footprint "res, 0805, HD")
      (description "RES SMD 2.2K OHM 1% 1/8W 0805")
      (fields (field (name "RESISTANCE") "2.2KΩ"))
      (libsource (lib "Master JULY2019") (part "Res,0805,2.2KΩ,±1%,100.0 ppm/°C,150.0 V,CRCW08052K20FKEA"))
    )
    (comp (ref "R30")
      (value "CR0805-JW-330ELF")
      (footprint "res, 0805, HD")
      (description "RES SMD 33 OHM 5% 1/8W 0805")
      (fields
        (field (name "MANUFACTURER") "Bourns Inc.")
        (field (name "TOLERANCE") "±5%")
        (field (name "RESISTANCE") "33Ω")
      )
      (libsource (lib "Master JULY2019") (part "Res,0805,33Ω,±5%,200ppm,CR0805-JW-330ELF"))
    )
    (comp (ref "R32")
      (value "Vishay / Dale CRCW080510K0FKTA")
      (footprint "res, 0805, HD")
      (description "RES SMD 10K OHM 1% 1/8W 0805")
      (fields (field (name "RESISTANCE") "10KΩ"))
      (libsource (lib "Master Oct28_2018") (part "Res,0805,10.0kΩ,1%,100 ppm,CRCW080510K0FKTA"))
    )
    (comp (ref "R33")
      (value "Res1")
      (footprint "res, 0805, HD")
      (description "RES SMD 3.32K OHM 1% 1/8W 0805")
      (fields (field (name "RESISTANCE") "3.32KΩ"))
      (libsource (lib "Master JULY2019") (part "Res,0805,3.32K,±1%,100.0 ppm/°C,150.0 V,CRCW08053K32FKEA"))
    )
    (comp (ref "R34")
      (value "Vishay / Dale CRCW080510K0FKTA")
      (footprint "res, 0805, HD")
      (description "RES SMD 10K OHM 1% 1/8W 0805")
      (fields (field (name "RESISTANCE") "10KΩ"))
      (libsource (lib "Master Oct28_2018") (part "Res,0805,10.0kΩ,1%,100 ppm,CRCW080510K0FKTA"))
    )
    (comp (ref "R35")
      (value "Res,0805,100kΩ,1%,100ppm,CRCW0805100KFKEA")
      (footprint "res, 0805, HD")
      (description "100 kOhms ±1% 0.125W, 1/8W Chip Resistor 0805 (2012 Metric) Thick Film")
      (fields
        (field (name "MANUFACTURER PART NUMBER") "CRCW0805100KFKEA")
        (field (name "MANUFACTURER") "Vishay")
        (field (name "RESISTANCE") "100 kΩ")
      )
      (libsource (lib "Master Oct28_2018") (part "Res,0805,100kΩ,1%,100ppm,CRCW0805100KFKEA"))
    )
    (comp (ref "R36")
      (value "Res,0805,100kΩ,1%,100ppm,CRCW0805100KFKEA")
      (footprint "res, 0805, HD")
      (description "100 kOhms ±1% 0.125W, 1/8W Chip Resistor 0805 (2012 Metric) Thick Film")
      (fields
        (field (name "MANUFACTURER PART NUMBER") "CRCW0805100KFKEA")
        (field (name "MANUFACTURER") "Vishay")
        (field (name "RESISTANCE") "100 kΩ")
      )
      (libsource (lib "Master Oct28_2018") (part "Res,0805,100kΩ,1%,100ppm,CRCW0805100KFKEA"))
    )
    (comp (ref "R37")
      (value "Vishay CRCW08051K00JNEA")
      (footprint "res, 0805, HD")
      (description "Res Thick Film 0805 1K Ohm 5% 0.125W(1/8W) ±200ppm/C Molded SMD Automotive Paper T/R")
      (fields
        (field (name "MANUFACTURER PART NUMBER") "CRCW08051K00JNEA")
        (field (name "RESISTANCE") "1.00 kΩ")
      )
      (libsource (lib "Master Oct28_2018") (part "Res,0805,1.00 kΩ,5%,200ppm,CRCW08051K00JNEA"))
    )
    (comp (ref "R38")
      (value "Vishay CRCW08051K00JNEA")
      (footprint "res, 0805, HD")
      (description "Res Thick Film 0805 1K Ohm 5% 0.125W(1/8W) ±200ppm/C Molded SMD Automotive Paper T/R")
      (fields
        (field (name "MANUFACTURER PART NUMBER") "CRCW08051K00JNEA")
        (field (name "RESISTANCE") "1.00 kΩ")
      )
      (libsource (lib "Master Oct28_2018") (part "Res,0805,1.00 kΩ,5%,200ppm,CRCW08051K00JNEA"))
    )
    (comp (ref "R40")
      (value "Res1")
      (footprint "res, 0805, HD")
      (fields (field (name "RESISTANCE") "120k"))
      (libsource (lib "Master SEPT2019") (part "Res,0805,Generic"))
    )
    (comp (ref "R41")
      (value "Res,0805,100kΩ,1%,100ppm,CRCW0805100KFKEA")
      (footprint "res, 0805, HD")
      (description "100 kOhms ±1% 0.125W, 1/8W Chip Resistor 0805 (2012 Metric) Thick Film")
      (fields
        (field (name "MANUFACTURER PART NUMBER") "CRCW0805100KFKEA")
        (field (name "MANUFACTURER") "Vishay")
        (field (name "RESISTANCE") "100 kΩ")
        (field (name "USED") "N/S")
      )
      (libsource (lib "Master Oct28_2018") (part "Res,0805,100kΩ,1%,100ppm,CRCW0805100KFKEA"))
    )
    (comp (ref "R44")
      (value "Vishay CRCW08051K00JNEA")
      (footprint "res, 0805, HD")
      (description "Res Thick Film 0805 1K Ohm 5% 0.125W(1/8W) ±200ppm/C Molded SMD Automotive Paper T/R")
      (fields
        (field (name "MANUFACTURER PART NUMBER") "CRCW08051K00JNEA")
        (field (name "RESISTANCE") "1.00 kΩ")
      )
      (libsource (lib "Master Oct28_2018") (part "Res,0805,1.00 kΩ,5%,200ppm,CRCW08051K00JNEA"))
    )
    (comp (ref "R45")
      (value "Res1")
      (footprint "res, 0805, HD")
      (fields (field (name "RESISTANCE") "1.8k"))
      (libsource (lib "Master SEPT2019") (part "Res,0805,Generic"))
    )
    (comp (ref "R46")
      (value "Res,0805,2.2Ohm,5%,200ppm,RMCF0805JT2R20")
      (footprint "res, 0805, HD")
      (description "RES 2.2 OHM 5% 1/8W 0805")
      (fields (field (name "TOLERANCE") "5%") (field (name "RESISTANCE") "2.2Ω"))
      (libsource (lib "Master Mar2021") (part "Res,0805,2.2Ohm,5%,200ppm,RMCF0805JT2R20"))
    )
    (comp (ref "R47")
      (value "Vishay / Dale CRCW080510K0FKTA")
      (footprint "res, 0805, HD")
      (description "RES SMD 10K OHM 1% 1/8W 0805")
      (fields (field (name "RESISTANCE") "10KΩ"))
      (libsource (lib "Master SEPT2019") (part "Res,0805,10.0kΩ,1%,100 ppm,CRCW080510K0FKTA"))
    )
    (comp (ref "R48")
      (value "Res,0805,2.2Ohm,5%,200ppm,RMCF0805JT2R20")
      (footprint "res, 0805, HD")
      (description "RES 2.2 OHM 5% 1/8W 0805")
      (fields (field (name "TOLERANCE") "5%") (field (name "RESISTANCE") "2.2Ω"))
      (libsource (lib "Master Mar2021") (part "Res,0805,2.2Ohm,5%,200ppm,RMCF0805JT2R20"))
    )
    (comp (ref "R49")
      (value "Vishay CRCW08051K00JNEA")
      (footprint "res, 0805, HD")
      (description "Res Thick Film 0805 1K Ohm 5% 0.125W(1/8W) ±200ppm/C Molded SMD Automotive Paper T/R")
      (fields
        (field (name "MANUFACTURER PART NUMBER") "CRCW08051K00JNEA")
        (field (name "RESISTANCE") "1.00 kΩ")
      )
      (libsource (lib "Master Oct28_2018") (part "Res,0805,1.00 kΩ,5%,200ppm,CRCW08051K00JNEA"))
    )
    (comp (ref "R54")
      (value "Res1")
      (footprint "res, 0805, HD")
      (description "RES SMD 3.32K OHM 1% 1/8W 0805")
      (fields (field (name "RESISTANCE") "3.32KΩ"))
      (libsource (lib "Master JULY2019") (part "Res,0805,3.32K,±1%,100.0 ppm/°C,150.0 V,CRCW08053K32FKEA"))
    )
    (comp (ref "R56")
      (value "Res1")
      (footprint "res, 0805, HD")
      (description "RES SMD 0.0 OHM JUMPER 1/3W 0805")
      (fields (field (name "RESISTANCE") "0.0 Ω"))
      (libsource (lib "Master SEPT2019") (part "Res,0805,0.0Ω,150V"))
    )
    (comp (ref "R57")
      (value "Res1")
      (footprint "res, 0805, HD")
      (description "RES SMD 0.0 OHM JUMPER 1/3W 0805")
      (fields (field (name "RESISTANCE") "0.0 Ω"))
      (libsource (lib "Master SEPT2019") (part "Res,0805,0.0Ω,150V"))
    )
    (comp (ref "U1")
      (value "AOZ1280CI")
      (footprint "SOT23-6")
      (description "IC,VR,Buck In 3V-26V,Vo Adj 1.2A,AOZ1280CI,SOT-23-6")
      (fields (field (name "MANUFACTURER") "Alpha & Omega Semiconductor Inc"))
      (libsource (lib "Master JULY2019") (part "Controller,Buck Reg,3-26V,1.2A,SOT23,AOZ1280CI"))
    )
    (comp (ref "U2")
      (value "REF2030AIDDCR")
      (footprint "SOT23-5")
      (description "IC VREF SERIES 1.5V/3V 5SOT")
      (fields (field (name "TOLERANCE") "±0.05%"))
      (libsource (lib "Master JULY2019") (part "Ref, 1.5V/3V, 5-3.02VdcIn, 20mA,REF2030AIDDCR"))
    )
    (comp (ref "U3")
      (value "TLV70333DBVR")
      (footprint "SOT23-5")
      (description "IC REG LINEAR 3.3V 300MA SOT23-5")
      (libsource (lib "Master JULY2019") (part "Reg, LDO, 3.3V fixed, 5.5-3.3Vdc In, 0.3mA,TLV703"))
    )
    (comp (ref "U4")
      (value "AD5242BRUZ100-RL7")
      (footprint "TSSOP-16")
      (description "Digital Potentiometer 100k Ohm 2 Circuit 256 Taps I²C Interface 16-TSSOP")
      (fields
        (field (name "MANUFACTURER") "Analog Devices Inc.")
        (field (name "TOLERANCE") "-30%, +50%")
        (field (name "MFG ~{P}N") "AD5242BRUZ100-RL7")
      )
      (libsource (lib "Master Mar2024") (part "IC,Dual Digital POT,100K,256 Taps,I2C,AD5242BRUZ100-RL7"))
    )
    (comp (ref "U5")
      (value "INA180A1IDBVR")
      (footprint "SOT23-5")
      (description "Current Sense Amplifier 1 Circuit Rail-to-Rail SOT-23-5")
      (fields (field (name "MANUFACTURER") "Texas Instruments"))
      (libsource (lib "Master JUL_2019-Shawn") (part "OPAMP,CurrentMon,20V/V,350kHz,SOT-23-5,I INA180A1IDBVR"))
    )
    (comp (ref "U6")
      (value "TSV911ILT")
      (footprint "SOT23-5")
      (description "General Purpose Amplifier 1 Circuit Rail-to-Rail SOT-23-5")
      (fields (field (name "MFG P/N") "TSV911ILT"))
      (libsource (lib "Master JULY2019") (part "Opamp,SOT5, 8Mhz, Rail to Rail, TSV911ILT"))
    )
    (comp (ref "U7")
      (value "opto,TCMT1109")
      (footprint "SSOP, 4-Leads")
      (description "Optocoupler DC-IN 1-CH Transistor DC-OUT 4-Pin Mini-Flat T/R")
      (libsource (lib "Master JULY2019") (part "opto,TCMT1109"))
    )
    (comp (ref "U8")
      (value "MKL26Z64VFT4")
      (footprint "48-VFQFN Exposed Pad")
      (description "IC MCU 32BIT 64KB FLASH 48QFN")
      (fields
        (field (name "MANUFACTURER") "NXP USA Inc.")
        (field (name "BASE PART NUMBER") "MKL26Z64")
        (field (name "MFG P/N") "MKL26Z64VFT4")
      )
      (libsource (lib "Master JULY2019") (part "Micro,Teensy,48Mhz,32Bit,64KB,MKL26Z64VFT4"))
    )
    (comp (ref "U12")
      (value "LM7321MF/NOPB")
      (footprint "SOT23-5")
      (libsource (lib "Master JULY2019") (part "OPAMP,20Mhz,MOSFET DRIVER,SOT23-5,LM7321MF"))
    )
    (comp (ref "XTAL1")
      (value "NX3225SA-16.000000MHZ-B3")
      (footprint "CRYSTAL,4-SMD, No Lead")
      (description "CRYSTAL 16.0000MHZ 7.2PF SMD")
      (fields (field (name "MANUFACTURER") "NDK America, Inc."))
      (libsource (lib "Master JULY2019") (part "resonator,crystal,SMD,stab15ppm,Tol,10ppm,7.2pf,80ohms,NX3225SA-16.000000MHZ-B3"))
    )
  )
  (nets
    (net (code "1") (name "+3.3V") (class "Default")
      (node (ref "C10") (pin "2") (pinfunction "2_2") (pintype "passive"))
      (node (ref "C11") (pin "1") (pinfunction "1_1") (pintype "passive"))
      (node (ref "C13") (pin "2") (pinfunction "2_2") (pintype "passive"))
      (node (ref "C17") (pin "2") (pinfunction "2_2") (pintype "passive"))
      (node (ref "C18") (pin "2") (pinfunction "2_2") (pintype "passive"))
      (node (ref "C19") (pin "2") (pinfunction "2_2") (pintype "passive"))
      (node (ref "C20") (pin "2") (pinfunction "2_2") (pintype "passive"))
      (node (ref "C43") (pin "2") (pinfunction "2_2") (pintype "passive"))
      (node (ref "J1") (pin "3") (pinfunction "3_3") (pintype "passive"))
      (node (ref "J6") (pin "2") (pinfunction "2_2") (pintype "passive"))
      (node (ref "MOD1") (pin "9") (pinfunction "3v3_9") (pintype "passive"))
      (node (ref "Q14") (pin "1") (pinfunction "G_1") (pintype "passive"))
      (node (ref "Q15") (pin "1") (pinfunction "G_1") (pintype "passive"))
      (node (ref "R33") (pin "2") (pinfunction "2_2") (pintype "passive"))
      (node (ref "R54") (pin "2") (pinfunction "2_2") (pintype "passive"))
      (node (ref "U2") (pin "3") (pinfunction "EN_3") (pintype "passive"))
      (node (ref "U2") (pin "4") (pinfunction "Vin_4") (pintype "passive"))
      (node (ref "U3") (pin "5") (pinfunction "OUT_5") (pintype "passive"))
      (node (ref "U5") (pin "5") (pinfunction "VS_5") (pintype "passive"))
      (node (ref "U6") (pin "5") (pinfunction "+Vin_5") (pintype "passive"))
      (node (ref "U8") (pin "1") (pinfunction "VCC_1") (pintype "bidirectional"))
      (node (ref "U8") (pin "22") (pinfunction "VCC_22") (pintype "bidirectional"))
      (node (ref "U8") (pin "5") (pinfunction "VOUT3V3_5") (pintype "bidirectional"))
      (node (ref "U8") (pin "9") (pinfunction "VCCA_9") (pintype "bidirectional"))
    )
    (net (code "2") (name "+5V") (class "Default")
      (node (ref "C16") (pin "2") (pinfunction "2_2") (pintype "passive"))
      (node (ref "C30") (pin "2") (pinfunction "2_2") (pintype "passive"))
      (node (ref "C8") (pin "2") (pinfunction "2_2") (pintype "passive"))
      (node (ref "C9") (pin "1") (pinfunction "1_1") (pintype "passive"))
      (node (ref "L1") (pin "2") (pinfunction "2_2") (pintype "passive"))
      (node (ref "R1") (pin "2") (pinfunction "2_2") (pintype "passive"))
      (node (ref "R20") (pin "2") (pinfunction "2_2") (pintype "passive"))
      (node (ref "R3") (pin "2") (pinfunction "2_2") (pintype "passive"))
      (node (ref "R56") (pin "2") (pinfunction "2_2") (pintype "passive"))
      (node (ref "U3") (pin "1") (pinfunction "IN_1") (pintype "passive"))
      (node (ref "U3") (pin "3") (pinfunction "EN_3") (pintype "passive"))
    )
    (net (code "3") (name "+12") (class "Default")
      (node (ref "C2") (pin "2") (pinfunction "2_2") (pintype "passive"))
      (node (ref "C3") (pin "2") (pinfunction "2_2") (pintype "passive"))
      (node (ref "C35") (pin "2") (pinfunction "2_2") (pintype "passive"))
      (node (ref "J5") (pin "2") (pinfunction "2_2") (pintype "passive"))
      (node (ref "R34") (pin "2") (pinfunction "2_2") (pintype "passive"))
      (node (ref "R35") (pin "2") (pinfunction "2_2") (pintype "passive"))
      (node (ref "R5") (pin "2") (pinfunction "2_2") (pintype "passive"))
      (node (ref "R6") (pin "2") (pinfunction "2_2") (pintype "passive"))
      (node (ref "R7") (pin "2") (pinfunction "2_2") (pintype "passive"))
      (node (ref "R8") (pin "2") (pinfunction "2_2") (pintype "passive"))
      (node (ref "U1") (pin "4") (pinfunction "EN_4") (pintype "input"))
      (node (ref "U1") (pin "5") (pinfunction "VIN_5") (pintype "input"))
      (node (ref "U12") (pin "5") (pinfunction "V+_5") (pintype "power_in"))
    )
    (net (code "4") (name "/Boot_PTA7") (class "Default")
      (node (ref "MOD1") (pin "5") (pinfunction "PTA7_5") (pintype "passive"))
      (node (ref "U8") (pin "20") (pinfunction "SWD-IO_20") (pintype "bidirectional"))
    )
    (net (code "5") (name "/Boot_PTB0") (class "Default")
      (node (ref "MOD1") (pin "6") (pinfunction "PTB0_6") (pintype "passive"))
      (node (ref "U8") (pin "17") (pinfunction "SWD-CLK_17") (pintype "bidirectional"))
    )
    (net (code "6") (name "/Boot_PTB1") (class "Default")
      (node (ref "MOD1") (pin "7") (pinfunction "PTB1_7") (pintype "passive"))
    )
    (net (code "7") (name "/Boot_RST") (class "Default")
      (node (ref "MOD1") (pin "8") (pinfunction "Reset_8") (pintype "passive"))
      (node (ref "U8") (pin "26") (pinfunction "RESET_26") (pintype "bidirectional"))
    )
    (net (code "8") (name "/Boot_VUSB") (class "Default")
      (node (ref "C33") (pin "2") (pinfunction "2_2") (pintype "passive"))
      (node (ref "MOD1") (pin "1") (pinfunction "VUSB_1") (pintype "passive"))
      (node (ref "U8") (pin "6") (pinfunction "VREGIN_6") (pintype "bidirectional"))
    )
    (net (code "9") (name "/CMPEN_OP") (class "Default")
      (node (ref "C25") (pin "1") (pinfunction "1_1") (pintype "passive"))
      (node (ref "C36") (pin "1") (pinfunction "1_1") (pintype "passive"))
      (node (ref "R32") (pin "2") (pinfunction "2_2") (pintype "passive"))
      (node (ref "R41") (pin "1") (pinfunction "1_1") (pintype "passive"))
      (node (ref "R46") (pin "2") (pinfunction "2_2") (pintype "passive"))
      (node (ref "R48") (pin "2") (pinfunction "2_2") (pintype "passive"))
      (node (ref "U12") (pin "1") (pinfunction "OUT_1") (pintype "output"))
    )
    (net (code "10") (name "/DiffPair_Boot_D_N") (class "Default")
      (node (ref "MOD1") (pin "3") (pinfunction "D-_3") (pintype "passive"))
      (node (ref "R27") (pin "1") (pinfunction "1_1") (pintype "passive"))
    )
    (net (code "11") (name "/DiffPair_Boot_D_P") (class "Default")
      (node (ref "MOD1") (pin "2") (pinfunction "D+_2") (pintype "passive"))
      (node (ref "R30") (pin "1") (pinfunction "1_1") (pintype "passive"))
    )
    (net (code "12") (name "/DiffPair_Micro_D_N") (class "Default")
      (node (ref "R27") (pin "2") (pinfunction "2_2") (pintype "passive"))
      (node (ref "U8") (pin "4") (pinfunction "USB-M_4") (pintype "bidirectional"))
    )
    (net (code "13") (name "/DiffPair_Micro_D_P") (class "Default")
      (node (ref "R30") (pin "2") (pinfunction "2_2") (pintype "passive"))
      (node (ref "U8") (pin "3") (pinfunction "USB-P_3") (pintype "bidirectional"))
    )
    (net (code "14") (name "/Digi_I_HI_GD") (class "Default")
      (node (ref "R37") (pin "1") (pinfunction "1_1") (pintype "passive"))
      (node (ref "U8") (pin "19") (pinfunction "D4/INT/TOUCH/PWM_19") (pintype "bidirectional"))
    )
    (net (code "15") (name "/Digi_I_LO_GD") (class "Default")
      (node (ref "R13") (pin "1") (pinfunction "1_1") (pintype "passive"))
      (node (ref "U8") (pin "41") (pinfunction "D2/INT_41") (pintype "bidirectional"))
    )
    (net (code "16") (name "/Digi_I_MED_GD") (class "Default")
      (node (ref "R15") (pin "1") (pinfunction "1_1") (pintype "passive"))
      (node (ref "U8") (pin "18") (pinfunction "D3/INT/TOUCH/PWM_18") (pintype "bidirectional"))
    )
    (net (code "17") (name "/Digi_LD_GateCntrl") (class "Default")
      (node (ref "R49") (pin "1") (pinfunction "1_1") (pintype "passive"))
      (node (ref "U8") (pin "48") (pinfunction "D5/INT/20MA_48") (pintype "bidirectional"))
    )
    (net (code "18") (name "/ExternalCntrl") (class "Default")
      (node (ref "J7") (pin "1") (pinfunction "1_1") (pintype "passive"))
      (node (ref "J8") (pin "1") (pinfunction "1_1") (pintype "passive"))
      (node (ref "R29") (pin "2") (pinfunction "2_2") (pintype "passive"))
    )
    (net (code "19") (name "/Gate_DRV_A") (class "Default")
      (node (ref "J4") (pin "1") (pintype "passive"))
      (node (ref "R46") (pin "1") (pinfunction "1_1") (pintype "passive"))
    )
    (net (code "20") (name "/Gate_DRV_B") (class "Default")
      (node (ref "J4") (pin "2") (pintype "passive"))
      (node (ref "R48") (pin "1") (pinfunction "1_1") (pintype "passive"))
    )
    (net (code "21") (name "/I_ADJ_Man") (class "Default")
      (node (ref "J6") (pin "4") (pinfunction "4_4") (pintype "passive"))
      (node (ref "R38") (pin "1") (pinfunction "1_1") (pintype "passive"))
    )
    (net (code "22") (name "/I_HI_GD") (class "Default")
      (node (ref "J4") (pin "6") (pintype "passive"))
      (node (ref "Q11") (pin "3") (pinfunction "C_3") (pintype "passive"))
      (node (ref "R34") (pin "1") (pinfunction "1_1") (pintype "passive"))
      (node (ref "R36") (pin "2") (pinfunction "2_2") (pintype "passive"))
    )
    (net (code "23") (name "/I_LO_GD") (class "Default")
      (node (ref "J4") (pin "8") (pintype "passive"))
      (node (ref "Q3") (pin "3") (pinfunction "C_3") (pintype "passive"))
      (node (ref "R11") (pin "2") (pinfunction "2_2") (pintype "passive"))
      (node (ref "R5") (pin "1") (pinfunction "1_1") (pintype "passive"))
    )
    (net (code "24") (name "/I_MED_GD") (class "Default")
      (node (ref "J4") (pin "7") (pintype "passive"))
      (node (ref "Q4") (pin "3") (pinfunction "C_3") (pintype "passive"))
      (node (ref "R12") (pin "2") (pinfunction "2_2") (pintype "passive"))
      (node (ref "R6") (pin "1") (pinfunction "1_1") (pintype "passive"))
    )
    (net (code "25") (name "/Iref") (class "Default")
      (node (ref "R47") (pin "2") (pinfunction "2_2") (pintype "passive"))
      (node (ref "U8") (pin "14") (pinfunction "D26/A12/DAC_14") (pintype "bidirectional"))
    )
    (net (code "26") (name "/Iref_filt") (class "Default")
      (node (ref "C12") (pin "2") (pinfunction "2_2") (pintype "passive"))
      (node (ref "Q2") (pin "3") (pinfunction "D_3") (pintype "passive"))
      (node (ref "R47") (pin "1") (pinfunction "1_1") (pintype "passive"))
      (node (ref "U12") (pin "3") (pinfunction "IN+_3") (pintype "input"))
      (node (ref "U7") (pin "4") (pinfunction "C_4") (pintype "passive"))
    )
    (net (code "27") (name "/Isense") (class "Default")
      (node (ref "R23") (pin "2") (pinfunction "2_2") (pintype "passive"))
      (node (ref "R44") (pin "1") (pinfunction "1_1") (pintype "passive"))
      (node (ref "U5") (pin "1") (pinfunction "Out_1") (pintype "passive"))
    )
    (net (code "28") (name "/Isense(+)") (class "Default")
      (node (ref "J2") (pin "2") (pinfunction "2_2") (pintype "passive"))
      (node (ref "U5") (pin "3") (pinfunction "IN+_3") (pintype "passive"))
    )
    (net (code "29") (name "/Isense(-)") (class "Default")
      (node (ref "J2") (pin "1") (pinfunction "1_1") (pintype "passive"))
      (node (ref "U5") (pin "4") (pinfunction "IN-_4") (pintype "passive"))
    )
    (net (code "30") (name "/Isense_filt") (class "Default")
      (node (ref "C38") (pin "2") (pinfunction "2_2") (pintype "passive"))
      (node (ref "R23") (pin "1") (pinfunction "1_1") (pintype "passive"))
      (node (ref "R40") (pin "2") (pinfunction "2_2") (pintype "passive"))
    )
    (net (code "31") (name "/POT_IIC_Active") (class "Default")
      (node (ref "R9") (pin "2") (pinfunction "2_2") (pintype "passive"))
      (node (ref "U8") (pin "45") (pinfunction "D6/INT/PWM_45") (pintype "bidirectional"))
    )
    (net (code "32") (name "/SCL") (class "Default")
      (node (ref "J1") (pin "1") (pinfunction "1_1") (pintype "passive"))
      (node (ref "Q14") (pin "2") (pinfunction "S_2") (pintype "passive"))
      (node (ref "R33") (pin "1") (pinfunction "1_1") (pintype "passive"))
      (node (ref "U8") (pin "34") (pinfunction "D22/A8/SCL1/TOUCH/PWM_34") (pintype "bidirectional"))
    )
    (net (code "33") (name "/SCL_Dpot") (class "Default")
      (node (ref "R10") (pin "2") (pinfunction "2_2") (pintype "passive"))
      (node (ref "R3") (pin "1") (pinfunction "1_1") (pintype "passive"))
      (node (ref "U4") (pin "5") (pinfunction "VDD_5") (pintype "passive"))
    )
    (net (code "34") (name "/SDA") (class "Default")
      (node (ref "J1") (pin "2") (pinfunction "2_2") (pintype "passive"))
      (node (ref "Q15") (pin "2") (pinfunction "S_2") (pintype "passive"))
      (node (ref "R54") (pin "1") (pinfunction "1_1") (pintype "passive"))
      (node (ref "U8") (pin "35") (pinfunction "D23/A9/SDA1/TOUCH/PWM_35") (pintype "bidirectional"))
    )
    (net (code "35") (name "/SDA_Dpot") (class "Default")
      (node (ref "R14") (pin "2") (pinfunction "2_2") (pintype "passive"))
      (node (ref "R20") (pin "1") (pinfunction "1_1") (pintype "passive"))
      (node (ref "U4") (pin "11") (pinfunction "DGND_11") (pintype "passive"))
    )
    (net (code "36") (name "/Temp Sense") (class "Default")
      (node (ref "J4") (pin "5") (pintype "passive"))
      (node (ref "R21") (pin "1") (pinfunction "1_1") (pintype "passive"))
      (node (ref "R28") (pin "1") (pinfunction "1_1") (pintype "passive"))
    )
    (net (code "37") (name "/V_LD_Sense_A") (class "Default")
      (node (ref "C45") (pin "2") (pinfunction "2_2") (pintype "passive"))
      (node (ref "J3") (pin "2") (pintype "passive"))
      (node (ref "R25") (pin "2") (pinfunction "2_2") (pintype "passive"))
    )
    (net (code "38") (name "/V_LD_Sense_B") (class "Default")
      (node (ref "C44") (pin "2") (pinfunction "2_2") (pintype "passive"))
      (node (ref "J3") (pin "7") (pintype "passive"))
      (node (ref "R22") (pin "2") (pinfunction "2_2") (pintype "passive"))
    )
    (net (code "39") (name "/Vsense") (class "Default")
      (node (ref "C23") (pin "1") (pinfunction "1_1") (pintype "passive"))
      (node (ref "R24") (pin "2") (pinfunction "2_2") (pintype "passive"))
      (node (ref "R26") (pin "1") (pinfunction "1_1") (pintype "passive"))
      (node (ref "U6") (pin "1") (pinfunction "1OUT_1") (pintype "output"))
    )
    (net (code "40") (name "1.5V") (class "Default")
      (node (ref "C16") (pin "1") (pinfunction "1_1") (pintype "passive"))
      (node (ref "C31") (pin "2") (pinfunction "2_2") (pintype "passive"))
      (node (ref "C4") (pin "1") (pinfunction "1_1") (pintype "passive"))
      (node (ref "C42") (pin "1") (pinfunction "1_1") (pintype "passive"))
      (node (ref "C5") (pin "2") (pinfunction "2_2") (pintype "passive"))
      (node (ref "R4") (pin "1") (pinfunction "1_1") (pintype "passive"))
      (node (ref "U2") (pin "1") (pinfunction "Vbias_1") (pintype "passive"))
    )
    (net (code "41") (name "3V") (class "Default")
      (node (ref "C32") (pin "2") (pinfunction "2_2") (pintype "passive"))
      (node (ref "C39") (pin "2") (pinfunction "2_2") (pintype "passive"))
      (node (ref "C6") (pin "1") (pinfunction "1_1") (pintype "passive"))
      (node (ref "C7") (pin "2") (pinfunction "2_2") (pintype "passive"))
      (node (ref "D4") (pin "2") (pinfunction "K_2") (pintype "passive"))
      (node (ref "D6") (pin "2") (pinfunction "K_2") (pintype "passive"))
      (node (ref "R21") (pin "2") (pinfunction "2_2") (pintype "passive"))
      (node (ref "U2") (pin "5") (pinfunction "Vref_5") (pintype "passive"))
      (node (ref "U8") (pin "10") (pinfunction "VREF-H_10") (pintype "bidirectional"))
    )
    (net (code "42") (name "ExtrnCNTRL_RTN") (class "Default")
      (node (ref "J7") (pin "2") (pinfunction "2_2") (pintype "passive"))
      (node (ref "J8") (pin "2") (pinfunction "2_2") (pintype "passive"))
      (node (ref "U7") (pin "2") (pinfunction "K_2") (pintype "passive"))
    )
    (net (code "43") (name "GND") (class "Default")
      (node (ref "C10") (pin "1") (pinfunction "1_1") (pintype "passive"))
      (node (ref "C11") (pin "2") (pinfunction "2_2") (pintype "passive"))
      (node (ref "C12") (pin "1") (pinfunction "1_1") (pintype "passive"))
      (node (ref "C13") (pin "1") (pinfunction "1_1") (pintype "passive"))
      (node (ref "C14") (pin "1") (pinfunction "1_1") (pintype "passive"))
      (node (ref "C17") (pin "1") (pinfunction "1_1") (pintype "passive"))
      (node (ref "C18") (pin "1") (pinfunction "1_1") (pintype "passive"))
      (node (ref "C19") (pin "1") (pinfunction "1_1") (pintype "passive"))
      (node (ref "C2") (pin "1") (pinfunction "1_1") (pintype "passive"))
      (node (ref "C20") (pin "1") (pinfunction "1_1") (pintype "passive"))
      (node (ref "C21") (pin "1") (pinfunction "1_1") (pintype "passive"))
      (node (ref "C22") (pin "1") (pinfunction "1_1") (pintype "passive"))
      (node (ref "C24") (pin "1") (pinfunction "1_1") (pintype "passive"))
      (node (ref "C26") (pin "1") (pinfunction "1_1") (pintype "passive"))
      (node (ref "C3") (pin "1") (pinfunction "1_1") (pintype "passive"))
      (node (ref "C30") (pin "1") (pinfunction "1_1") (pintype "passive"))
      (node (ref "C31") (pin "1") (pinfunction "1_1") (pintype "passive"))
      (node (ref "C32") (pin "1") (pinfunction "1_1") (pintype "passive"))
      (node (ref "C33") (pin "1") (pinfunction "1_1") (pintype "passive"))
      (node (ref "C35") (pin "1") (pinfunction "1_1") (pintype "passive"))
      (node (ref "C38") (pin "1") (pinfunction "1_1") (pintype "passive"))
      (node (ref "C39") (pin "1") (pinfunction "1_1") (pintype "passive"))
      (node (ref "C4") (pin "2") (pinfunction "2_2") (pintype "passive"))
      (node (ref "C43") (pin "1") (pinfunction "1_1") (pintype "passive"))
      (node (ref "C44") (pin "1") (pinfunction "1_1") (pintype "passive"))
      (node (ref "C45") (pin "1") (pinfunction "1_1") (pintype "passive"))
      (node (ref "C5") (pin "1") (pinfunction "1_1") (pintype "passive"))
      (node (ref "C6") (pin "2") (pinfunction "2_2") (pintype "passive"))
      (node (ref "C7") (pin "1") (pinfunction "1_1") (pintype "passive"))
      (node (ref "C8") (pin "1") (pinfunction "1_1") (pintype "passive"))
      (node (ref "C9") (pin "2") (pinfunction "2_2") (pintype "passive"))
      (node (ref "D1") (pin "2") (pinfunction "A_2") (pintype "passive"))
      (node (ref "D4") (pin "1") (pinfunction "A_1") (pintype "passive"))
      (node (ref "D6") (pin "1") (pinfunction "A_1") (pintype "passive"))
      (node (ref "J2") (pin "3") (pinfunction "3_3") (pintype "passive"))
      (node (ref "J3") (pin "4") (pintype "passive"))
      (node (ref "J3") (pin "5") (pintype "passive"))
      (node (ref "J4") (pin "3") (pintype "passive"))
      (node (ref "J4") (pin "4") (pintype "passive"))
      (node (ref "J5") (pin "1") (pinfunction "1_1") (pintype "passive"))
      (node (ref "J6") (pin "1") (pinfunction "1_1") (pintype "passive"))
      (node (ref "MOD1") (pin "10") (pinfunction "GND_10") (pintype "passive"))
      (node (ref "Q1") (pin "2") (pinfunction "S_2") (pintype "passive"))
      (node (ref "Q11") (pin "2") (pinfunction "E_2") (pintype "passive"))
      (node (ref "Q12") (pin "2") (pinfunction "E_2") (pintype "passive"))
      (node (ref "Q2") (pin "2") (pinfunction "S_2") (pintype "passive"))
      (node (ref "Q3") (pin "2") (pinfunction "E_2") (pintype "passive"))
      (node (ref "Q4") (pin "2") (pinfunction "E_2") (pintype "passive"))
      (node (ref "Q5") (pin "2") (pinfunction "E_2") (pintype "passive"))
      (node (ref "Q6") (pin "2") (pinfunction "E_2") (pintype "passive"))
      (node (ref "R11") (pin "1") (pinfunction "1_1") (pintype "passive"))
      (node (ref "R12") (pin "1") (pinfunction "1_1") (pintype "passive"))
      (node (ref "R16") (pin "1") (pinfunction "1_1") (pintype "passive"))
      (node (ref "R2") (pin "1") (pinfunction "1_1") (pintype "passive"))
      (node (ref "R24") (pin "1") (pinfunction "1_1") (pintype "passive"))
      (node (ref "R32") (pin "1") (pinfunction "1_1") (pintype "passive"))
      (node (ref "R36") (pin "1") (pinfunction "1_1") (pintype "passive"))
      (node (ref "U1") (pin "2") (pinfunction "GND_2") (pintype "input"))
      (node (ref "U12") (pin "2") (pinfunction "V-_2") (pintype "power_in"))
      (node (ref "U2") (pin "2") (pinfunction "GND_2") (pintype "passive"))
      (node (ref "U3") (pin "2") (pinfunction "GND_2") (pintype "passive"))
      (node (ref "U5") (pin "2") (pinfunction "GND_2") (pintype "passive"))
      (node (ref "U6") (pin "2") (pinfunction "-Vin_2") (pintype "passive"))
      (node (ref "U7") (pin "3") (pinfunction "E_3") (pintype "passive"))
      (node (ref "U8") (pin "11") (pinfunction "VREF-L_11") (pintype "bidirectional"))
      (node (ref "U8") (pin "12") (pinfunction "VSSA_12") (pintype "bidirectional"))
      (node (ref "U8") (pin "2") (pinfunction "VSS_2") (pintype "bidirectional"))
      (node (ref "U8") (pin "23") (pinfunction "VSS_23") (pintype "bidirectional"))
      (node (ref "U8") (pin "49") (pinfunction "VSS_49") (pintype "bidirectional"))
      (node (ref "XTAL1") (pin "2") (pinfunction "GND_2") (pintype "passive"))
      (node (ref "XTAL1") (pin "4") (pinfunction "4_4") (pintype "passive"))
    )
    (net (code "44") (name "Net-(C36-Pad2)") (class "Default")
      (node (ref "C36") (pin "2") (pinfunction "2_2") (pintype "passive"))
      (node (ref "R45") (pin "1") (pinfunction "1_1") (pintype "passive"))
    )
    (net (code "45") (name "Net-(D1-K)") (class "Default")
      (node (ref "C1") (pin "1") (pinfunction "1_1") (pintype "passive"))
      (node (ref "D1") (pin "1") (pinfunction "K_1") (pintype "passive"))
      (node (ref "L1") (pin "1") (pinfunction "1_1") (pintype "passive"))
      (node (ref "U1") (pin "6") (pinfunction "LX_6") (pintype "output"))
    )
    (net (code "46") (name "Net-(D4-AK)") (class "Default")
      (node (ref "C42") (pin "2") (pinfunction "2_2") (pintype "passive"))
      (node (ref "D4") (pin "3") (pinfunction "AK_3") (pintype "passive"))
      (node (ref "R22") (pin "1") (pinfunction "1_1") (pintype "passive"))
      (node (ref "U6") (pin "3") (pinfunction "1IN+_3") (pintype "input"))
    )
    (net (code "47") (name "Net-(D6-AK)") (class "Default")
      (node (ref "C23") (pin "2") (pinfunction "2_2") (pintype "passive"))
      (node (ref "D6") (pin "3") (pinfunction "AK_3") (pintype "passive"))
      (node (ref "R25") (pin "1") (pinfunction "1_1") (pintype "passive"))
      (node (ref "U6") (pin "4") (pinfunction "1IN-_4") (pintype "input"))
    )
    (net (code "48") (name "Net-(Q1-D)") (class "Default")
      (node (ref "C14") (pin "2") (pinfunction "2_2") (pintype "passive"))
      (node (ref "Q1") (pin "3") (pinfunction "D_3") (pintype "passive"))
      (node (ref "R4") (pin "2") (pinfunction "2_2") (pintype "passive"))
      (node (ref "R57") (pin "1") (pinfunction "1_1") (pintype "passive"))
    )
    (net (code "49") (name "Net-(Q1-G)") (class "Default")
      (node (ref "Q1") (pin "1") (pinfunction "G_1") (pintype "passive"))
      (node (ref "R16") (pin "2") (pinfunction "2_2") (pintype "passive"))
      (node (ref "R9") (pin "1") (pinfunction "1_1") (pintype "passive"))
    )
    (net (code "50") (name "Net-(Q2-G)") (class "Default")
      (node (ref "Q2") (pin "1") (pinfunction "G_1") (pintype "passive"))
      (node (ref "R49") (pin "2") (pinfunction "2_2") (pintype "passive"))
    )
    (net (code "51") (name "Net-(Q3-B)") (class "Default")
      (node (ref "Q3") (pin "1") (pinfunction "B_1") (pintype "passive"))
      (node (ref "Q5") (pin "3") (pinfunction "C_3") (pintype "passive"))
      (node (ref "R7") (pin "1") (pinfunction "1_1") (pintype "passive"))
    )
    (net (code "52") (name "Net-(Q4-B)") (class "Default")
      (node (ref "Q4") (pin "1") (pinfunction "B_1") (pintype "passive"))
      (node (ref "Q6") (pin "3") (pinfunction "C_3") (pintype "passive"))
      (node (ref "R8") (pin "1") (pinfunction "1_1") (pintype "passive"))
    )
    (net (code "53") (name "Net-(Q5-B)") (class "Default")
      (node (ref "Q5") (pin "1") (pinfunction "B_1") (pintype "passive"))
      (node (ref "R13") (pin "2") (pinfunction "2_2") (pintype "passive"))
    )
    (net (code "54") (name "Net-(Q6-B)") (class "Default")
      (node (ref "Q6") (pin "1") (pinfunction "B_1") (pintype "passive"))
      (node (ref "R15") (pin "2") (pinfunction "2_2") (pintype "passive"))
    )
    (net (code "55") (name "Net-(Q11-B)") (class "Default")
      (node (ref "Q11") (pin "1") (pinfunction "B_1") (pintype "passive"))
      (node (ref "Q12") (pin "3") (pinfunction "C_3") (pintype "passive"))
      (node (ref "R35") (pin "1") (pinfunction "1_1") (pintype "passive"))
    )
    (net (code "56") (name "Net-(Q12-B)") (class "Default")
      (node (ref "Q12") (pin "1") (pinfunction "B_1") (pintype "passive"))
      (node (ref "R37") (pin "2") (pinfunction "2_2") (pintype "passive"))
    )
    (net (code "57") (name "Net-(Q14-D)") (class "Default")
      (node (ref "Q14") (pin "3") (pinfunction "D_3") (pintype "passive"))
      (node (ref "R10") (pin "1") (pinfunction "1_1") (pintype "passive"))
    )
    (net (code "58") (name "Net-(Q15-D)") (class "Default")
      (node (ref "Q15") (pin "3") (pinfunction "D_3") (pintype "passive"))
      (node (ref "R14") (pin "1") (pinfunction "1_1") (pintype "passive"))
    )
    (net (code "59") (name "Net-(U1-BST)") (class "Default")
      (node (ref "C1") (pin "2") (pinfunction "2_2") (pintype "passive"))
      (node (ref "U1") (pin "1") (pinfunction "BST_1") (pintype "input"))
    )
    (net (code "60") (name "Net-(U1-FB)") (class "Default")
      (node (ref "R1") (pin "1") (pinfunction "1_1") (pintype "passive"))
      (node (ref "R2") (pin "2") (pinfunction "2_2") (pintype "passive"))
      (node (ref "U1") (pin "3") (pinfunction "FB_3") (pintype "input"))
    )
    (net (code "61") (name "Net-(U4A-O1)") (class "Default")
      (node (ref "R56") (pin "1") (pinfunction "1_1") (pintype "passive"))
      (node (ref "R57") (pin "2") (pinfunction "2_2") (pintype "passive"))
      (node (ref "U4") (pin "1") (pinfunction "O1_1") (pintype "passive"))
    )
    (net (code "62") (name "Net-(U7-A)") (class "Default")
      (node (ref "R29") (pin "1") (pinfunction "1_1") (pintype "passive"))
      (node (ref "U7") (pin "1") (pinfunction "A_1") (pintype "passive"))
    )
    (net (code "63") (name "Net-(U8-D15{slash}A1{slash}INT{slash}TOUCH)") (class "Default")
      (node (ref "C26") (pin "2") (pinfunction "2_2") (pintype "passive"))
      (node (ref "R38") (pin "2") (pinfunction "2_2") (pintype "passive"))
      (node (ref "U8") (pin "33") (pinfunction "D15/A1/INT/TOUCH_33") (pintype "bidirectional"))
    )
    (net (code "64") (name "Net-(U8-D16{slash}A2{slash}TOUCH{slash}20MA)") (class "Default")
      (node (ref "C21") (pin "2") (pinfunction "2_2") (pintype "passive"))
      (node (ref "R44") (pin "2") (pinfunction "2_2") (pintype "passive"))
      (node (ref "U8") (pin "27") (pinfunction "D16/A2/TOUCH/20MA_27") (pintype "bidirectional"))
    )
    (net (code "65") (name "Net-(U8-D17{slash}A3{slash}TOUCH{slash}PWM{slash}20MA)") (class "Default")
      (node (ref "C22") (pin "2") (pinfunction "2_2") (pintype "passive"))
      (node (ref "R26") (pin "2") (pinfunction "2_2") (pintype "passive"))
      (node (ref "U8") (pin "28") (pinfunction "D17/A3/TOUCH/PWM/20MA_28") (pintype "bidirectional"))
    )
    (net (code "66") (name "Net-(U8-D18{slash}A4{slash}SDA0{slash}TOUCH)") (class "Default")
      (node (ref "C24") (pin "2") (pinfunction "2_2") (pintype "passive"))
      (node (ref "R28") (pin "2") (pinfunction "2_2") (pintype "passive"))
      (node (ref "U8") (pin "30") (pinfunction "D18/A4/SDA0/TOUCH_30") (pintype "bidirectional"))
    )
    (net (code "67") (name "Net-(U8-OSC1)") (class "Default")
      (node (ref "U8") (pin "24") (pinfunction "OSC1_24") (pintype "bidirectional"))
      (node (ref "XTAL1") (pin "1") (pinfunction "1_1") (pintype "passive"))
    )
    (net (code "68") (name "Net-(U8-OSC2)") (class "Default")
      (node (ref "U8") (pin "25") (pinfunction "OSC2_25") (pintype "bidirectional"))
      (node (ref "XTAL1") (pin "3") (pinfunction "3_3") (pintype "passive"))
    )
    (net (code "69") (name "Net-(U12-IN-)") (class "Default")
      (node (ref "C25") (pin "2") (pinfunction "2_2") (pintype "passive"))
      (node (ref "R40") (pin "1") (pinfunction "1_1") (pintype "passive"))
      (node (ref "R41") (pin "2") (pinfunction "2_2") (pintype "passive"))
      (node (ref "R45") (pin "2") (pinfunction "2_2") (pintype "passive"))
      (node (ref "U12") (pin "4") (pinfunction "IN-_4") (pintype "input"))
    )
    (net (code "70") (name "unconnected-(J3-Pad1)") (class "Default")
      (node (ref "J3") (pin "1") (pintype "passive"))
    )
    (net (code "71") (name "unconnected-(J3-Pad3)") (class "Default")
      (node (ref "J3") (pin "3") (pintype "passive"))
    )
    (net (code "72") (name "unconnected-(J3-Pad6)") (class "Default")
      (node (ref "J3") (pin "6") (pintype "passive"))
    )
    (net (code "73") (name "unconnected-(J3-Pad8)") (class "Default")
      (node (ref "J3") (pin "8") (pintype "passive"))
    )
    (net (code "74") (name "unconnected-(J6-Pad3)") (class "Default")
      (node (ref "J6") (pin "3") (pinfunction "3_3") (pintype "passive"))
    )
    (net (code "75") (name "unconnected-(MOD1-PTA6-Pad4)") (class "Default")
      (node (ref "MOD1") (pin "4") (pinfunction "PTA6_4") (pintype "passive+no_connect"))
    )
    (net (code "76") (name "unconnected-(U3-NC-Pad4)") (class "Default")
      (node (ref "U3") (pin "4") (pinfunction "NC_4") (pintype "passive+no_connect"))
    )
    (net (code "77") (name "unconnected-(U4A-AD0-Pad9)") (class "Default")
      (node (ref "U4") (pin "9") (pinfunction "AD0_9") (pintype "passive"))
    )
    (net (code "78") (name "unconnected-(U4A-AD1-Pad10)") (class "Default")
      (node (ref "U4") (pin "10") (pinfunction "AD1_10") (pintype "passive"))
    )
    (net (code "79") (name "unconnected-(U4A-O2-Pad13)") (class "Default")
      (node (ref "U4") (pin "13") (pinfunction "O2_13") (pintype "passive"))
    )
    (net (code "80") (name "unconnected-(U4A-SCL-Pad7)") (class "Default")
      (node (ref "U4") (pin "7") (pinfunction "SCL_7") (pintype "passive"))
    )
    (net (code "81") (name "unconnected-(U4A-SDA-Pad8)") (class "Default")
      (node (ref "U4") (pin "8") (pinfunction "SDA_8") (pintype "passive"))
    )
    (net (code "82") (name "unconnected-(U4A-VSS-Pad12)") (class "Default")
      (node (ref "U4") (pin "12") (pinfunction "VSS_12") (pintype "passive"))
    )
    (net (code "83") (name "unconnected-(U4A-~{SHDN}-Pad6)") (class "Default")
      (node (ref "U4") (pin "6") (pinfunction "~{SHDN}_6") (pintype "passive"))
    )
    (net (code "84") (name "unconnected-(U4B-A2-Pad16)") (class "Default")
      (node (ref "U4") (pin "16") (pinfunction "A2_16") (pintype "passive"))
    )
    (net (code "85") (name "unconnected-(U4B-B2-Pad14)") (class "Default")
      (node (ref "U4") (pin "14") (pinfunction "B2_14") (pintype "passive"))
    )
    (net (code "86") (name "unconnected-(U4B-W2-Pad15)") (class "Default")
      (node (ref "U4") (pin "15") (pinfunction "W2_15") (pintype "passive"))
    )
    (net (code "87") (name "unconnected-(U4C-A1-Pad2)") (class "Default")
      (node (ref "U4") (pin "2") (pinfunction "A1_2") (pintype "passive"))
    )
    (net (code "88") (name "unconnected-(U4C-B1-Pad4)") (class "Default")
      (node (ref "U4") (pin "4") (pinfunction "B1_4") (pintype "passive"))
    )
    (net (code "89") (name "unconnected-(U4C-W1-Pad3)") (class "Default")
      (node (ref "U4") (pin "3") (pinfunction "W1_3") (pintype "passive"))
    )
    (net (code "90") (name "unconnected-(U8-D0{slash}RX1{slash}MOSI1{slash}TOUCH-Pad31)") (class "Default")
      (node (ref "U8") (pin "31") (pinfunction "D0/RX1/MOSI1/TOUCH_31") (pintype "bidirectional"))
    )
    (net (code "91") (name "unconnected-(U8-D1{slash}TX1{slash}MISO1{slash}TOUCH-Pad32)") (class "Default")
      (node (ref "U8") (pin "32") (pinfunction "D1/TX1/MISO1/TOUCH_32") (pintype "bidirectional"))
    )
    (net (code "92") (name "unconnected-(U8-D7{slash}RX3{slash}INT-Pad43)") (class "Default")
      (node (ref "U8") (pin "43") (pinfunction "D7/RX3/INT_43") (pintype "bidirectional"))
    )
    (net (code "93") (name "unconnected-(U8-D8{slash}TX3{slash}INT-Pad44)") (class "Default")
      (node (ref "U8") (pin "44") (pinfunction "D8/TX3/INT_44") (pintype "bidirectional"))
    )
    (net (code "94") (name "unconnected-(U8-D9{slash}RX2{slash}INT{slash}PWM-Pad36)") (class "Default")
      (node (ref "U8") (pin "36") (pinfunction "D9/RX2/INT/PWM_36") (pintype "bidirectional"))
    )
    (net (code "95") (name "unconnected-(U8-D10{slash}TX2{slash}INT{slash}PWM-Pad37)") (class "Default")
      (node (ref "U8") (pin "37") (pinfunction "D10/TX2/INT/PWM_37") (pintype "bidirectional"))
    )
    (net (code "96") (name "unconnected-(U8-D11{slash}MOSI0{slash}INT-Pad39)") (class "Default")
      (node (ref "U8") (pin "39") (pinfunction "D11/MOSI0/INT_39") (pintype "bidirectional"))
    )
    (net (code "97") (name "unconnected-(U8-D12{slash}MISO0{slash}INT-Pad40)") (class "Default")
      (node (ref "U8") (pin "40") (pinfunction "D12/MISO0/INT_40") (pintype "bidirectional"))
    )
    (net (code "98") (name "unconnected-(U8-D13{slash}SCK0{slash}INT-Pad38)") (class "Default")
      (node (ref "U8") (pin "38") (pinfunction "D13/SCK0/INT_38") (pintype "bidirectional"))
    )
    (net (code "99") (name "unconnected-(U8-D14{slash}A0{slash}INT-Pad42)") (class "Default")
      (node (ref "U8") (pin "42") (pinfunction "D14/A0/INT_42") (pintype "bidirectional"))
    )
    (net (code "100") (name "unconnected-(U8-D19{slash}A5{slash}SCL0{slash}TOUCH-Pad29)") (class "Default")
      (node (ref "U8") (pin "29") (pinfunction "D19/A5/SCL0/TOUCH_29") (pintype "bidirectional"))
    )
    (net (code "101") (name "unconnected-(U8-D20{slash}A6{slash}SCK1{slash}PWM-Pad46)") (class "Default")
      (node (ref "U8") (pin "46") (pinfunction "D20/A6/SCK1/PWM_46") (pintype "bidirectional"))
    )
    (net (code "102") (name "unconnected-(U8-D21{slash}A7{slash}20MA-Pad47)") (class "Default")
      (node (ref "U8") (pin "47") (pinfunction "D21/A7/20MA_47") (pintype "bidirectional"))
    )
    (net (code "103") (name "unconnected-(U8-D24{slash}A10-Pad7)") (class "Default")
      (node (ref "U8") (pin "7") (pinfunction "D24/A10_7") (pintype "bidirectional"))
    )
    (net (code "104") (name "unconnected-(U8-D25{slash}A11-Pad8)") (class "Default")
      (node (ref "U8") (pin "8") (pinfunction "D25/A11_8") (pintype "bidirectional"))
    )
    (net (code "105") (name "unconnected-(U8-NMI-B-Pad21)") (class "Default")
      (node (ref "U8") (pin "21") (pinfunction "NMI-B_21") (pintype "bidirectional"))
    )
    (net (code "106") (name "unconnected-(U8-PTE24-Pad15)") (class "Default")
      (node (ref "U8") (pin "15") (pinfunction "PTE24_15") (pintype "bidirectional"))
    )
    (net (code "107") (name "unconnected-(U8-PTE25-Pad16)") (class "Default")
      (node (ref "U8") (pin "16") (pinfunction "PTE25_16") (pintype "bidirectional"))
    )
    (net (code "108") (name "unconnected-(U8-PTE29-Pad13)") (class "Default")
      (node (ref "U8") (pin "13") (pinfunction "PTE29_13") (pintype "bidirectional"))
    )
  )
)
